# Mother_Board_FPGA.net
KiCad netlist of a schematic drawn in Altium Designer
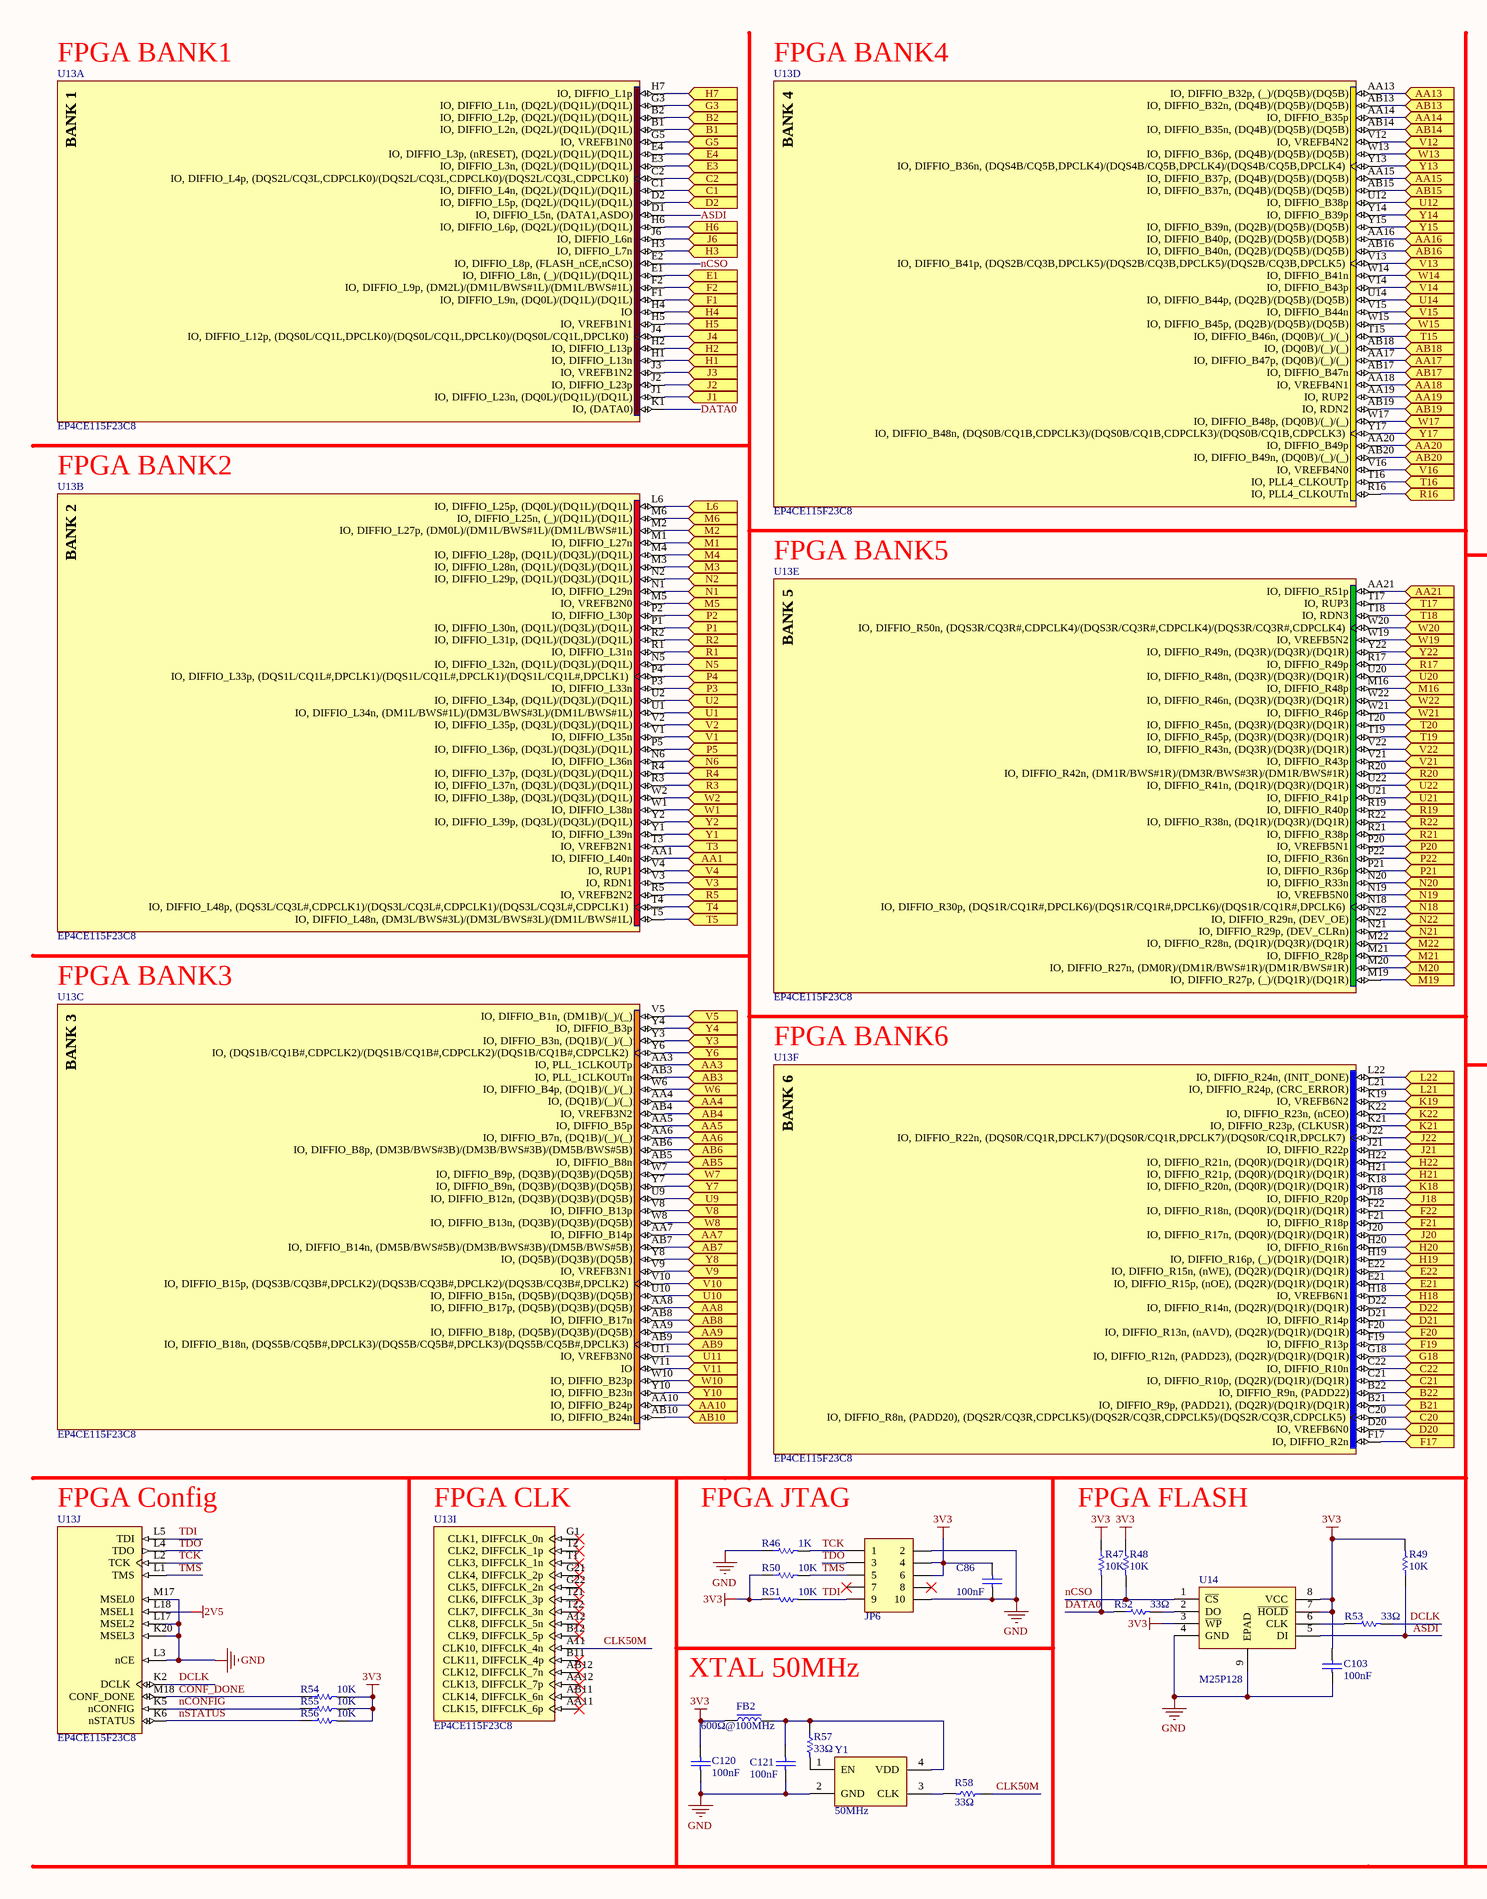
[diagram p0: Mother Board FPGA.SchDoc, left]
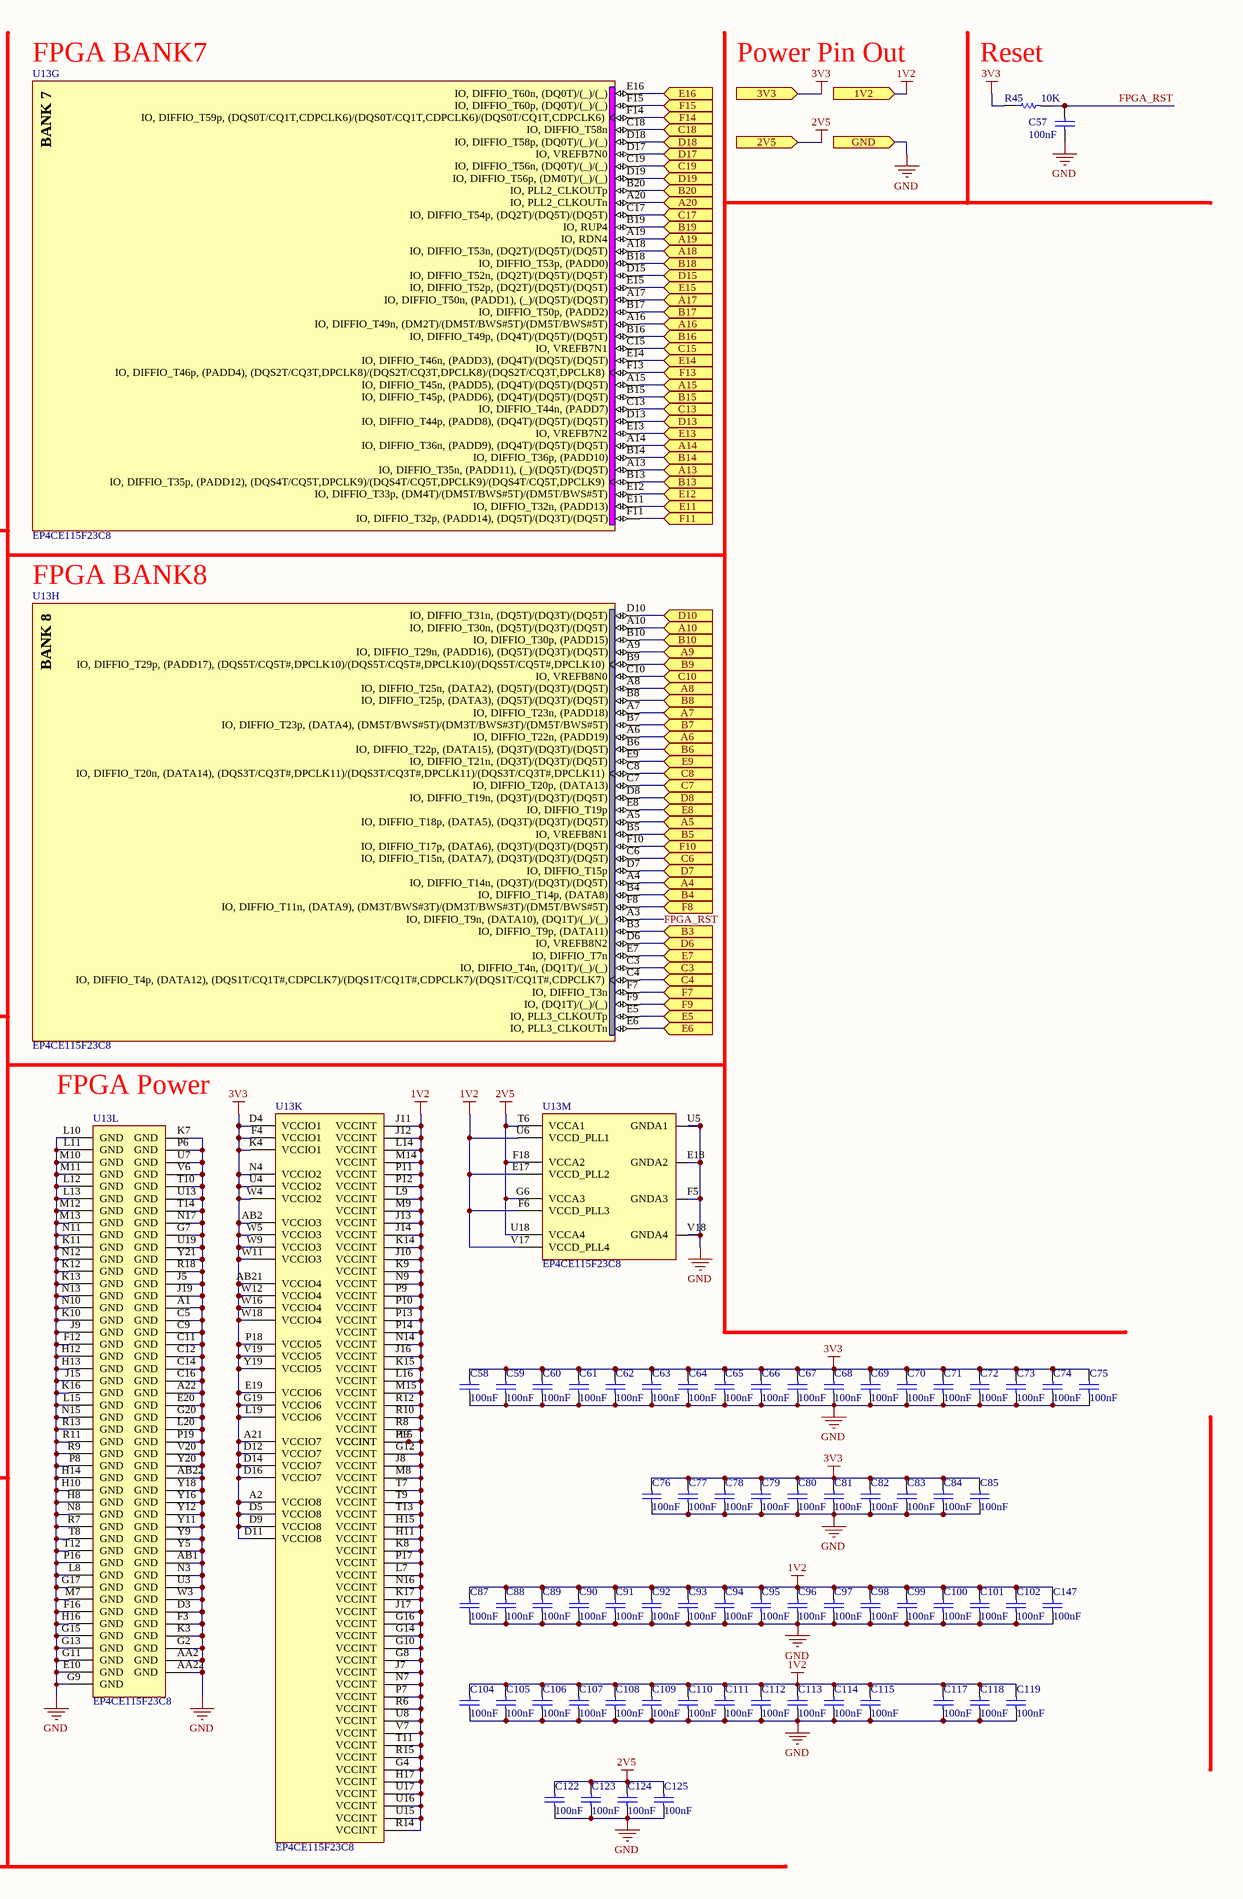
[diagram p1: Mother Board FPGA.SchDoc, right]

(export (version "E")
  (design (tool "Eeschema 10.0.6"))
  (components
    (comp (ref "C57") (value "100nF") (footprint "C0402") (libsource (lib "Cap") (part "Cap")))
    (comp (ref "C58") (value "100nF") (footprint "C0402") (libsource (lib "Cap") (part "Cap")))
    (comp (ref "C59") (value "100nF") (footprint "C0402") (libsource (lib "Cap") (part "Cap")))
    (comp (ref "C60") (value "100nF") (footprint "C0402") (libsource (lib "Cap") (part "Cap")))
    (comp (ref "C61") (value "100nF") (footprint "C0402") (libsource (lib "Cap") (part "Cap")))
    (comp (ref "C62") (value "100nF") (footprint "C0402") (libsource (lib "Cap") (part "Cap")))
    (comp (ref "C63") (value "100nF") (footprint "C0402") (libsource (lib "Cap") (part "Cap")))
    (comp (ref "C64") (value "100nF") (footprint "C0402") (libsource (lib "Cap") (part "Cap")))
    (comp (ref "C65") (value "100nF") (footprint "C0402") (libsource (lib "Cap") (part "Cap")))
    (comp (ref "C66") (value "100nF") (footprint "C0402") (libsource (lib "Cap") (part "Cap")))
    (comp (ref "C67") (value "100nF") (footprint "C0402") (libsource (lib "Cap") (part "Cap")))
    (comp (ref "C68") (value "100nF") (footprint "C0402") (libsource (lib "Cap") (part "Cap")))
    (comp (ref "C69") (value "100nF") (footprint "C0402") (libsource (lib "Cap") (part "Cap")))
    (comp (ref "C70") (value "100nF") (footprint "C0402") (libsource (lib "Cap") (part "Cap")))
    (comp (ref "C71") (value "100nF") (footprint "C0402") (libsource (lib "Cap") (part "Cap")))
    (comp (ref "C72") (value "100nF") (footprint "C0402") (libsource (lib "Cap") (part "Cap")))
    (comp (ref "C73") (value "100nF") (footprint "C0402") (libsource (lib "Cap") (part "Cap")))
    (comp (ref "C74") (value "100nF") (footprint "C0402") (libsource (lib "Cap") (part "Cap")))
    (comp (ref "C75") (value "100nF") (footprint "C0402") (libsource (lib "Cap") (part "Cap")))
    (comp (ref "C76") (value "100nF") (footprint "C0402") (libsource (lib "Cap") (part "Cap")))
    (comp (ref "C77") (value "100nF") (footprint "C0402") (libsource (lib "Cap") (part "Cap")))
    (comp (ref "C78") (value "100nF") (footprint "C0402") (libsource (lib "Cap") (part "Cap")))
    (comp (ref "C79") (value "100nF") (footprint "C0402") (libsource (lib "Cap") (part "Cap")))
    (comp (ref "C80") (value "100nF") (footprint "C0402") (libsource (lib "Cap") (part "Cap")))
    (comp (ref "C81") (value "100nF") (footprint "C0402") (libsource (lib "Cap") (part "Cap")))
    (comp (ref "C82") (value "100nF") (footprint "C0402") (libsource (lib "Cap") (part "Cap")))
    (comp (ref "C83") (value "100nF") (footprint "C0402") (libsource (lib "Cap") (part "Cap")))
    (comp (ref "C84") (value "100nF") (footprint "C0402") (libsource (lib "Cap") (part "Cap")))
    (comp (ref "C85") (value "100nF") (footprint "C0402") (libsource (lib "Cap") (part "Cap")))
    (comp (ref "C86") (value "100nF") (footprint "C0603") (libsource (lib "Cap") (part "Cap")))
    (comp (ref "C87") (value "100nF") (footprint "C0402") (libsource (lib "Cap") (part "Cap")))
    (comp (ref "C88") (value "100nF") (footprint "C0402") (libsource (lib "Cap") (part "Cap")))
    (comp (ref "C89") (value "100nF") (footprint "C0402") (libsource (lib "Cap") (part "Cap")))
    (comp (ref "C90") (value "100nF") (footprint "C0402") (libsource (lib "Cap") (part "Cap")))
    (comp (ref "C91") (value "100nF") (footprint "C0402") (libsource (lib "Cap") (part "Cap")))
    (comp (ref "C92") (value "100nF") (footprint "C0402") (libsource (lib "Cap") (part "Cap")))
    (comp (ref "C93") (value "100nF") (footprint "C0402") (libsource (lib "Cap") (part "Cap")))
    (comp (ref "C94") (value "100nF") (footprint "C0402") (libsource (lib "Cap") (part "Cap")))
    (comp (ref "C95") (value "100nF") (footprint "C0402") (libsource (lib "Cap") (part "Cap")))
    (comp (ref "C96") (value "100nF") (footprint "C0402") (libsource (lib "Cap") (part "Cap")))
    (comp (ref "C97") (value "100nF") (footprint "C0402") (libsource (lib "Cap") (part "Cap")))
    (comp (ref "C98") (value "100nF") (footprint "C0402") (libsource (lib "Cap") (part "Cap")))
    (comp (ref "C99") (value "100nF") (footprint "C0402") (libsource (lib "Cap") (part "Cap")))
    (comp (ref "C100") (value "100nF") (footprint "C0402") (libsource (lib "Cap") (part "Cap")))
    (comp (ref "C101") (value "100nF") (footprint "C0402") (libsource (lib "Cap") (part "Cap")))
    (comp (ref "C102") (value "100nF") (footprint "C0402") (libsource (lib "Cap") (part "Cap")))
    (comp (ref "C103") (value "100nF") (footprint "C0603") (libsource (lib "Cap") (part "Cap")))
    (comp (ref "C104") (value "100nF") (footprint "C0402") (libsource (lib "Cap") (part "Cap")))
    (comp (ref "C105") (value "100nF") (footprint "C0402") (libsource (lib "Cap") (part "Cap")))
    (comp (ref "C106") (value "100nF") (footprint "C0402") (libsource (lib "Cap") (part "Cap")))
    (comp (ref "C107") (value "100nF") (footprint "C0402") (libsource (lib "Cap") (part "Cap")))
    (comp (ref "C108") (value "100nF") (footprint "C0402") (libsource (lib "Cap") (part "Cap")))
    (comp (ref "C109") (value "100nF") (footprint "C0402") (libsource (lib "Cap") (part "Cap")))
    (comp (ref "C110") (value "100nF") (footprint "C0402") (libsource (lib "Cap") (part "Cap")))
    (comp (ref "C111") (value "100nF") (footprint "C0402") (libsource (lib "Cap") (part "Cap")))
    (comp (ref "C112") (value "100nF") (footprint "C0402") (libsource (lib "Cap") (part "Cap")))
    (comp (ref "C113") (value "100nF") (footprint "C0402") (libsource (lib "Cap") (part "Cap")))
    (comp (ref "C114") (value "100nF") (footprint "C0402") (libsource (lib "Cap") (part "Cap")))
    (comp (ref "C115") (value "100nF") (footprint "C0402") (libsource (lib "Cap") (part "Cap")))
    (comp (ref "C117") (value "100nF") (footprint "C0402") (libsource (lib "Cap") (part "Cap")))
    (comp (ref "C118") (value "100nF") (footprint "C0402") (libsource (lib "Cap") (part "Cap")))
    (comp (ref "C119") (value "100nF") (footprint "C0402") (libsource (lib "Cap") (part "Cap")))
    (comp (ref "C120") (value "100nF") (footprint "C0603") (libsource (lib "Cap") (part "Cap")))
    (comp (ref "C121") (value "100nF") (footprint "C0603") (libsource (lib "Cap") (part "Cap")))
    (comp (ref "C122") (value "100nF") (footprint "C0402") (libsource (lib "Cap") (part "Cap")))
    (comp (ref "C123") (value "100nF") (footprint "C0402") (libsource (lib "Cap") (part "Cap")))
    (comp (ref "C124") (value "100nF") (footprint "C0402") (libsource (lib "Cap") (part "Cap")))
    (comp (ref "C125") (value "100nF") (footprint "C0402") (libsource (lib "Cap") (part "Cap")))
    (comp (ref "C147") (value "100nF") (footprint "C0402") (libsource (lib "Cap") (part "Cap")))
    (comp (ref "FB2")
      (value "600Ω@100MHz")
      (footprint "FB 0603")
      (description "磁珠")
      (libsource (lib "All lib") (part "FB"))
    )
    (comp (ref "JP6")
      (value "Header 5X2")
      (footprint "DC2.54-10P - L2")
      (description "5*2P接插件")
      (fields (field (name "版权归属") "源创客"))
      (libsource (lib "All lib") (part "Header 5PX2"))
    )
    (comp (ref "R45") (value "10K") (footprint "R0402") (libsource (lib "Res") (part "RES")))
    (comp (ref "R46") (value "1K") (footprint "R0603") (libsource (lib "Res") (part "RES")))
    (comp (ref "R47") (value "10K") (footprint "R0603") (libsource (lib "Res") (part "RES")))
    (comp (ref "R48") (value "10K") (footprint "R0603") (libsource (lib "Res") (part "RES")))
    (comp (ref "R49") (value "10K") (footprint "R0603") (libsource (lib "Res") (part "RES")))
    (comp (ref "R50") (value "10K") (footprint "R0603") (libsource (lib "Res") (part "RES")))
    (comp (ref "R51") (value "10K") (footprint "R0603") (libsource (lib "Res") (part "RES")))
    (comp (ref "R52") (value "33Ω") (footprint "R0603") (libsource (lib "Res") (part "RES")))
    (comp (ref "R53") (value "33Ω") (footprint "R0603") (libsource (lib "Res") (part "RES")))
    (comp (ref "R54") (value "10K") (footprint "R0402") (libsource (lib "Res") (part "RES")))
    (comp (ref "R55") (value "10K") (footprint "R0402") (libsource (lib "Res") (part "RES")))
    (comp (ref "R56") (value "10K") (footprint "R0402") (libsource (lib "Res") (part "RES")))
    (comp (ref "R57") (value "33Ω") (footprint "R0603") (libsource (lib "Res") (part "RES")))
    (comp (ref "R58") (value "33Ω") (footprint "R0603") (libsource (lib "Res") (part "RES")))
    (comp (ref "U13")
      (value "EP4CE115F23C8")
      (footprint "FBGA484")
      (fields (field (name "PUBLISHER") "Altium Limited"))
      (libsource (lib "All lib") (part "EP4CE115F23C8"))
    )
    (comp (ref "U14")
      (value "M25P128")
      (footprint "WSON8_8X6_MRN")
      (description "外置Flash")
      (fields (field (name "版权归属") "源创客"))
      (libsource (lib "All lib") (part "M25Pxx"))
    )
    (comp (ref "Y1")
      (value "50MHz")
      (footprint "XTAL-3225")
      (description "4脚有源晶振")
      (libsource (lib "All lib") (part "XTAL-4-Power"))
    )
  )
  (nets
    (net (code "1") (name "/A4") (class "Default")
      (node (ref "U13") (pin "A4") (pinfunction "IO,_DIFFIO_T14n,_(DQ3T)/(DQ3T)/(DQ5T)_A4") (pintype "bidirectional"))
    )
    (net (code "2") (name "/A5") (class "Default")
      (node (ref "U13") (pin "A5") (pinfunction "IO,_DIFFIO_T18p,_(DATA5),_(DQ3T)/(DQ3T)/(DQ5T)_A5") (pintype "bidirectional"))
    )
    (net (code "3") (name "/A6") (class "Default")
      (node (ref "U13") (pin "A6") (pinfunction "IO,_DIFFIO_T22n,_(PADD19)_A6") (pintype "bidirectional"))
    )
    (net (code "4") (name "/A7") (class "Default")
      (node (ref "U13") (pin "A7") (pinfunction "IO,_DIFFIO_T23n,_(PADD18)_A7") (pintype "bidirectional"))
    )
    (net (code "5") (name "/A8") (class "Default")
      (node (ref "U13") (pin "A8") (pinfunction "IO,_DIFFIO_T25n,_(DATA2),_(DQ5T)/(DQ3T)/(DQ5T)_A8") (pintype "bidirectional"))
    )
    (net (code "6") (name "/A9") (class "Default")
      (node (ref "U13") (pin "A9") (pinfunction "IO,_DIFFIO_T29n,_(PADD16),_(DQ5T)/(DQ3T)/(DQ5T)_A9") (pintype "bidirectional"))
    )
    (net (code "7") (name "/A10") (class "Default")
      (node (ref "U13") (pin "A10") (pinfunction "IO,_DIFFIO_T30n,_(DQ5T)/(DQ3T)/(DQ5T)_A10") (pintype "bidirectional"))
    )
    (net (code "8") (name "/A13") (class "Default")
      (node (ref "U13") (pin "A13") (pinfunction "IO,_DIFFIO_T35n,_(PADD11),_(_)/(DQ5T)/(DQ5T)_A13") (pintype "bidirectional"))
    )
    (net (code "9") (name "/A14") (class "Default")
      (node (ref "U13") (pin "A14") (pinfunction "IO,_DIFFIO_T36n,_(PADD9),_(DQ4T)/(DQ5T)/(DQ5T)_A14") (pintype "bidirectional"))
    )
    (net (code "10") (name "/A15") (class "Default")
      (node (ref "U13") (pin "A15") (pinfunction "IO,_DIFFIO_T45n,_(PADD5),_(DQ4T)/(DQ5T)/(DQ5T)_A15") (pintype "bidirectional"))
    )
    (net (code "11") (name "/A16") (class "Default")
      (node (ref "U13") (pin "A16") (pinfunction "IO,_DIFFIO_T49n,_(DM2T)/(DM5T/BWS#5T)/(DM5T/BWS#5T)_A16") (pintype "bidirectional"))
    )
    (net (code "12") (name "/A17") (class "Default")
      (node (ref "U13") (pin "A17") (pinfunction "IO,_DIFFIO_T50n,_(PADD1),_(_)/(DQ5T)/(DQ5T)_A17") (pintype "bidirectional"))
    )
    (net (code "13") (name "/A18") (class "Default")
      (node (ref "U13") (pin "A18") (pinfunction "IO,_DIFFIO_T53n,_(DQ2T)/(DQ5T)/(DQ5T)_A18") (pintype "bidirectional"))
    )
    (net (code "14") (name "/A19") (class "Default")
      (node (ref "U13") (pin "A19") (pinfunction "IO,_RDN4_A19") (pintype "bidirectional"))
    )
    (net (code "15") (name "/A20") (class "Default")
      (node (ref "U13") (pin "A20") (pinfunction "IO,_PLL2_CLKOUTn_A20") (pintype "bidirectional"))
    )
    (net (code "16") (name "/AA1") (class "Default")
      (node (ref "U13") (pin "AA1") (pinfunction "IO,_DIFFIO_L40n_AA1") (pintype "bidirectional"))
    )
    (net (code "17") (name "/AA3") (class "Default")
      (node (ref "U13") (pin "AA3") (pinfunction "IO,_PLL_1CLKOUTp_AA3") (pintype "bidirectional"))
    )
    (net (code "18") (name "/AA4") (class "Default")
      (node (ref "U13") (pin "AA4") (pinfunction "IO,_(DQ1B)/(_)/(_)_AA4") (pintype "bidirectional"))
    )
    (net (code "19") (name "/AA5") (class "Default")
      (node (ref "U13") (pin "AA5") (pinfunction "IO,_DIFFIO_B5p_AA5") (pintype "bidirectional"))
    )
    (net (code "20") (name "/AA6") (class "Default")
      (node (ref "U13") (pin "AA6") (pinfunction "IO,_DIFFIO_B7n,_(DQ1B)/(_)/(_)_AA6") (pintype "bidirectional"))
    )
    (net (code "21") (name "/AA7") (class "Default")
      (node (ref "U13") (pin "AA7") (pinfunction "IO,_DIFFIO_B14p_AA7") (pintype "bidirectional"))
    )
    (net (code "22") (name "/AA8") (class "Default")
      (node (ref "U13") (pin "AA8") (pinfunction "IO,_DIFFIO_B17p,_(DQ5B)/(DQ3B)/(DQ5B)_AA8") (pintype "bidirectional"))
    )
    (net (code "23") (name "/AA9") (class "Default")
      (node (ref "U13") (pin "AA9") (pinfunction "IO,_DIFFIO_B18p,_(DQ5B)/(DQ3B)/(DQ5B)_AA9") (pintype "bidirectional"))
    )
    (net (code "24") (name "/AA10") (class "Default")
      (node (ref "U13") (pin "AA10") (pinfunction "IO,_DIFFIO_B24p_AA10") (pintype "bidirectional"))
    )
    (net (code "25") (name "/AA13") (class "Default")
      (node (ref "U13") (pin "AA13") (pinfunction "IO,_DIFFIO_B32p,_(_)/(DQ5B)/(DQ5B)_AA13") (pintype "bidirectional"))
    )
    (net (code "26") (name "/AA14") (class "Default")
      (node (ref "U13") (pin "AA14") (pinfunction "IO,_DIFFIO_B35p_AA14") (pintype "bidirectional"))
    )
    (net (code "27") (name "/AA15") (class "Default")
      (node (ref "U13") (pin "AA15") (pinfunction "IO,_DIFFIO_B37p,_(DQ4B)/(DQ5B)/(DQ5B)_AA15") (pintype "bidirectional"))
    )
    (net (code "28") (name "/AA16") (class "Default")
      (node (ref "U13") (pin "AA16") (pinfunction "IO,_DIFFIO_B40p,_(DQ2B)/(DQ5B)/(DQ5B)_AA16") (pintype "bidirectional"))
    )
    (net (code "29") (name "/AA17") (class "Default")
      (node (ref "U13") (pin "AA17") (pinfunction "IO,_DIFFIO_B47p,_(DQ0B)/(_)/(_)_AA17") (pintype "bidirectional"))
    )
    (net (code "30") (name "/AA18") (class "Default")
      (node (ref "U13") (pin "AA18") (pinfunction "IO,_VREFB4N1_AA18") (pintype "bidirectional"))
    )
    (net (code "31") (name "/AA19") (class "Default")
      (node (ref "U13") (pin "AA19") (pinfunction "IO,_RUP2_AA19") (pintype "bidirectional"))
    )
    (net (code "32") (name "/AA20") (class "Default")
      (node (ref "U13") (pin "AA20") (pinfunction "IO,_DIFFIO_B49p_AA20") (pintype "bidirectional"))
    )
    (net (code "33") (name "/AA21") (class "Default")
      (node (ref "U13") (pin "AA21") (pinfunction "IO,_DIFFIO_R51p_AA21") (pintype "bidirectional"))
    )
    (net (code "34") (name "/AB3") (class "Default")
      (node (ref "U13") (pin "AB3") (pinfunction "IO,_PLL_1CLKOUTn_AB3") (pintype "bidirectional"))
    )
    (net (code "35") (name "/AB4") (class "Default")
      (node (ref "U13") (pin "AB4") (pinfunction "IO,_VREFB3N2_AB4") (pintype "bidirectional"))
    )
    (net (code "36") (name "/AB5") (class "Default")
      (node (ref "U13") (pin "AB5") (pinfunction "IO,_DIFFIO_B8n_AB5") (pintype "bidirectional"))
    )
    (net (code "37") (name "/AB6") (class "Default")
      (node (ref "U13") (pin "AB6") (pinfunction "IO,_DIFFIO_B8p,_(DM3B/BWS#3B)/(DM3B/BWS#3B)/(DM5B/BWS#5B)_AB6") (pintype "bidirectional"))
    )
    (net (code "38") (name "/AB7") (class "Default")
      (node (ref "U13") (pin "AB7") (pinfunction "IO,_DIFFIO_B14n,_(DM5B/BWS#5B)/(DM3B/BWS#3B)/(DM5B/BWS#5B)_AB7") (pintype "bidirectional"))
    )
    (net (code "39") (name "/AB8") (class "Default")
      (node (ref "U13") (pin "AB8") (pinfunction "IO,_DIFFIO_B17n_AB8") (pintype "bidirectional"))
    )
    (net (code "40") (name "/AB9") (class "Default")
      (node (ref "U13") (pin "AB9") (pinfunction "IO,_DIFFIO_B18n,_(DQS5B/CQ5B#,DPCLK3)/(DQS5B/CQ5B#,DPCLK3)/(DQS5B/CQ5B#,DPCLK3)_AB9") (pintype "bidirectional"))
    )
    (net (code "41") (name "/AB10") (class "Default")
      (node (ref "U13") (pin "AB10") (pinfunction "IO,_DIFFIO_B24n_AB10") (pintype "bidirectional"))
    )
    (net (code "42") (name "/AB13") (class "Default")
      (node (ref "U13") (pin "AB13") (pinfunction "IO,_DIFFIO_B32n,_(DQ4B)/(DQ5B)/(DQ5B)_AB13") (pintype "bidirectional"))
    )
    (net (code "43") (name "/AB14") (class "Default")
      (node (ref "U13") (pin "AB14") (pinfunction "IO,_DIFFIO_B35n,_(DQ4B)/(DQ5B)/(DQ5B)_AB14") (pintype "bidirectional"))
    )
    (net (code "44") (name "/AB15") (class "Default")
      (node (ref "U13") (pin "AB15") (pinfunction "IO,_DIFFIO_B37n,_(DQ4B)/(DQ5B)/(DQ5B)_AB15") (pintype "bidirectional"))
    )
    (net (code "45") (name "/AB16") (class "Default")
      (node (ref "U13") (pin "AB16") (pinfunction "IO,_DIFFIO_B40n,_(DQ2B)/(DQ5B)/(DQ5B)_AB16") (pintype "bidirectional"))
    )
    (net (code "46") (name "/AB17") (class "Default")
      (node (ref "U13") (pin "AB17") (pinfunction "IO,_DIFFIO_B47n_AB17") (pintype "bidirectional"))
    )
    (net (code "47") (name "/AB18") (class "Default")
      (node (ref "U13") (pin "AB18") (pinfunction "IO,_(DQ0B)/(_)/(_)_AB18") (pintype "bidirectional"))
    )
    (net (code "48") (name "/AB19") (class "Default")
      (node (ref "U13") (pin "AB19") (pinfunction "IO,_RDN2_AB19") (pintype "bidirectional"))
    )
    (net (code "49") (name "/AB20") (class "Default")
      (node (ref "U13") (pin "AB20") (pinfunction "IO,_DIFFIO_B49n,_(DQ0B)/(_)/(_)_AB20") (pintype "bidirectional"))
    )
    (net (code "50") (name "/ASDI") (class "Default")
      (node (ref "R49") (pin "1") (pinfunction "1_1") (pintype "passive"))
      (node (ref "U13") (pin "D1") (pinfunction "IO,_DIFFIO_L5n,_(DATA1,ASDO)_D1") (pintype "bidirectional"))
      (node (ref "U14") (pin "5") (pinfunction "DI_5") (pintype "passive"))
    )
    (net (code "51") (name "/B1") (class "Default")
      (node (ref "U13") (pin "B1") (pinfunction "IO,_DIFFIO_L2n,_(DQ2L)/(DQ1L)/(DQ1L)_B1") (pintype "bidirectional"))
    )
    (net (code "52") (name "/B2") (class "Default")
      (node (ref "U13") (pin "B2") (pinfunction "IO,_DIFFIO_L2p,_(DQ2L)/(DQ1L)/(DQ1L)_B2") (pintype "bidirectional"))
    )
    (net (code "53") (name "/B3") (class "Default")
      (node (ref "U13") (pin "B3") (pinfunction "IO,_DIFFIO_T9p,_(DATA11)_B3") (pintype "bidirectional"))
    )
    (net (code "54") (name "/B4") (class "Default")
      (node (ref "U13") (pin "B4") (pinfunction "IO,_DIFFIO_T14p,_(DATA8)_B4") (pintype "bidirectional"))
    )
    (net (code "55") (name "/B5") (class "Default")
      (node (ref "U13") (pin "B5") (pinfunction "IO,_VREFB8N1_B5") (pintype "bidirectional"))
    )
    (net (code "56") (name "/B6") (class "Default")
      (node (ref "U13") (pin "B6") (pinfunction "IO,_DIFFIO_T22p,_(DATA15),_(DQ3T)/(DQ3T)/(DQ5T)_B6") (pintype "bidirectional"))
    )
    (net (code "57") (name "/B7") (class "Default")
      (node (ref "U13") (pin "B7") (pinfunction "IO,_DIFFIO_T23p,_(DATA4),_(DM5T/BWS#5T)/(DM3T/BWS#3T)/(DM5T/BWS#5T)_B7") (pintype "bidirectional"))
    )
    (net (code "58") (name "/B8") (class "Default")
      (node (ref "U13") (pin "B8") (pinfunction "IO,_DIFFIO_T25p,_(DATA3),_(DQ5T)/(DQ3T)/(DQ5T)_B8") (pintype "bidirectional"))
    )
    (net (code "59") (name "/B9") (class "Default")
      (node (ref "U13") (pin "B9") (pinfunction "IO,_DIFFIO_T29p,_(PADD17),_(DQS5T/CQ5T#,DPCLK10)/(DQS5T/CQ5T#,DPCLK10)/(DQS5T/CQ5T#,DPCLK10)_B9") (pintype "bidirectional"))
    )
    (net (code "60") (name "/B10") (class "Default")
      (node (ref "U13") (pin "B10") (pinfunction "IO,_DIFFIO_T30p,_(PADD15)_B10") (pintype "bidirectional"))
    )
    (net (code "61") (name "/B13") (class "Default")
      (node (ref "U13") (pin "B13") (pinfunction "IO,_DIFFIO_T35p,_(PADD12),_(DQS4T/CQ5T,DPCLK9)/(DQS4T/CQ5T,DPCLK9)/(DQS4T/CQ5T,DPCLK9)_B13") (pintype "bidirectional"))
    )
    (net (code "62") (name "/B14") (class "Default")
      (node (ref "U13") (pin "B14") (pinfunction "IO,_DIFFIO_T36p,_(PADD10)_B14") (pintype "bidirectional"))
    )
    (net (code "63") (name "/B15") (class "Default")
      (node (ref "U13") (pin "B15") (pinfunction "IO,_DIFFIO_T45p,_(PADD6),_(DQ4T)/(DQ5T)/(DQ5T)_B15") (pintype "bidirectional"))
    )
    (net (code "64") (name "/B16") (class "Default")
      (node (ref "U13") (pin "B16") (pinfunction "IO,_DIFFIO_T49p,_(DQ4T)/(DQ5T)/(DQ5T)_B16") (pintype "bidirectional"))
    )
    (net (code "65") (name "/B17") (class "Default")
      (node (ref "U13") (pin "B17") (pinfunction "IO,_DIFFIO_T50p,_(PADD2)_B17") (pintype "bidirectional"))
    )
    (net (code "66") (name "/B18") (class "Default")
      (node (ref "U13") (pin "B18") (pinfunction "IO,_DIFFIO_T53p,_(PADD0)_B18") (pintype "bidirectional"))
    )
    (net (code "67") (name "/B19") (class "Default")
      (node (ref "U13") (pin "B19") (pinfunction "IO,_RUP4_B19") (pintype "bidirectional"))
    )
    (net (code "68") (name "/B20") (class "Default")
      (node (ref "U13") (pin "B20") (pinfunction "IO,_PLL2_CLKOUTp_B20") (pintype "bidirectional"))
    )
    (net (code "69") (name "/B21") (class "Default")
      (node (ref "U13") (pin "B21") (pinfunction "IO,_DIFFIO_R9p,_(PADD21),_(DQ2R)/(DQ1R)/(DQ1R)_B21") (pintype "bidirectional"))
    )
    (net (code "70") (name "/B22") (class "Default")
      (node (ref "U13") (pin "B22") (pinfunction "IO,_DIFFIO_R9n,_(PADD22)_B22") (pintype "bidirectional"))
    )
    (net (code "71") (name "/C1") (class "Default")
      (node (ref "U13") (pin "C1") (pinfunction "IO,_DIFFIO_L4n,_(DQ2L)/(DQ1L)/(DQ1L)_C1") (pintype "bidirectional"))
    )
    (net (code "72") (name "/C2") (class "Default")
      (node (ref "U13") (pin "C2") (pinfunction "IO,_DIFFIO_L4p,_(DQS2L/CQ3L,CDPCLK0)/(DQS2L/CQ3L,CDPCLK0)/(DQS2L/CQ3L,CDPCLK0)_C2") (pintype "bidirectional"))
    )
    (net (code "73") (name "/C3") (class "Default")
      (node (ref "U13") (pin "C3") (pinfunction "IO,_DIFFIO_T4n,_(DQ1T)/(_)/(_)_C3") (pintype "bidirectional"))
    )
    (net (code "74") (name "/C4") (class "Default")
      (node (ref "U13") (pin "C4") (pinfunction "IO,_DIFFIO_T4p,_(DATA12),_(DQS1T/CQ1T#,CDPCLK7)/(DQS1T/CQ1T#,CDPCLK7)/(DQS1T/CQ1T#,CDPCLK7)_C4") (pintype "bidirectional"))
    )
    (net (code "75") (name "/C6") (class "Default")
      (node (ref "U13") (pin "C6") (pinfunction "IO,_DIFFIO_T15n,_(DATA7),_(DQ3T)/(DQ3T)/(DQ5T)_C6") (pintype "bidirectional"))
    )
    (net (code "76") (name "/C7") (class "Default")
      (node (ref "U13") (pin "C7") (pinfunction "IO,_DIFFIO_T20p,_(DATA13)_C7") (pintype "bidirectional"))
    )
    (net (code "77") (name "/C8") (class "Default")
      (node (ref "U13") (pin "C8") (pinfunction "IO,_DIFFIO_T20n,_(DATA14),_(DQS3T/CQ3T#,DPCLK11)/(DQS3T/CQ3T#,DPCLK11)/(DQS3T/CQ3T#,DPCLK11)_C8") (pintype "bidirectional"))
    )
    (net (code "78") (name "/C10") (class "Default")
      (node (ref "U13") (pin "C10") (pinfunction "IO,_VREFB8N0_C10") (pintype "bidirectional"))
    )
    (net (code "79") (name "/C13") (class "Default")
      (node (ref "U13") (pin "C13") (pinfunction "IO,_DIFFIO_T44n,_(PADD7)_C13") (pintype "bidirectional"))
    )
    (net (code "80") (name "/C15") (class "Default")
      (node (ref "U13") (pin "C15") (pinfunction "IO,_VREFB7N1_C15") (pintype "bidirectional"))
    )
    (net (code "81") (name "/C17") (class "Default")
      (node (ref "U13") (pin "C17") (pinfunction "IO,_DIFFIO_T54p,_(DQ2T)/(DQ5T)/(DQ5T)_C17") (pintype "bidirectional"))
    )
    (net (code "82") (name "/C18") (class "Default")
      (node (ref "U13") (pin "C18") (pinfunction "IO,_DIFFIO_T58n_C18") (pintype "bidirectional"))
    )
    (net (code "83") (name "/C19") (class "Default")
      (node (ref "U13") (pin "C19") (pinfunction "IO,_DIFFIO_T56n,_(DQ0T)/(_)/(_)_C19") (pintype "bidirectional"))
    )
    (net (code "84") (name "/C20") (class "Default")
      (node (ref "U13") (pin "C20") (pinfunction "IO,_DIFFIO_R8n,_(PADD20),_(DQS2R/CQ3R,CDPCLK5)/(DQS2R/CQ3R,CDPCLK5)/(DQS2R/CQ3R,CDPCLK5)_C20") (pintype "bidirectional"))
    )
    (net (code "85") (name "/C21") (class "Default")
      (node (ref "U13") (pin "C21") (pinfunction "IO,_DIFFIO_R10p,_(DQ2R)/(DQ1R)/(DQ1R)_C21") (pintype "bidirectional"))
    )
    (net (code "86") (name "/C22") (class "Default")
      (node (ref "U13") (pin "C22") (pinfunction "IO,_DIFFIO_R10n_C22") (pintype "bidirectional"))
    )
    (net (code "87") (name "/CLK50M") (class "Default")
      (node (ref "R58") (pin "1") (pinfunction "1_1") (pintype "passive"))
      (node (ref "U13") (pin "A11") (pinfunction "CLK10,_DIFFCLK_4n_A11") (pintype "input"))
    )
    (net (code "88") (name "/CONF_DONE") (class "Default")
      (node (ref "R54") (pin "1") (pinfunction "1_1") (pintype "passive"))
      (node (ref "U13") (pin "M18") (pinfunction "CONF_DONE_M18") (pintype "bidirectional"))
    )
    (net (code "89") (name "/D2") (class "Default")
      (node (ref "U13") (pin "D2") (pinfunction "IO,_DIFFIO_L5p,_(DQ2L)/(DQ1L)/(DQ1L)_D2") (pintype "bidirectional"))
    )
    (net (code "90") (name "/D6") (class "Default")
      (node (ref "U13") (pin "D6") (pinfunction "IO,_VREFB8N2_D6") (pintype "bidirectional"))
    )
    (net (code "91") (name "/D7") (class "Default")
      (node (ref "U13") (pin "D7") (pinfunction "IO,_DIFFIO_T15p_D7") (pintype "bidirectional"))
    )
    (net (code "92") (name "/D8") (class "Default")
      (node (ref "U13") (pin "D8") (pinfunction "IO,_DIFFIO_T19n,_(DQ3T)/(DQ3T)/(DQ5T)_D8") (pintype "bidirectional"))
    )
    (net (code "93") (name "/D10") (class "Default")
      (node (ref "U13") (pin "D10") (pinfunction "IO,_DIFFIO_T31n,_(DQ5T)/(DQ3T)/(DQ5T)_D10") (pintype "bidirectional"))
    )
    (net (code "94") (name "/D13") (class "Default")
      (node (ref "U13") (pin "D13") (pinfunction "IO,_DIFFIO_T44p,_(PADD8),_(DQ4T)/(DQ5T)/(DQ5T)_D13") (pintype "bidirectional"))
    )
    (net (code "95") (name "/D15") (class "Default")
      (node (ref "U13") (pin "D15") (pinfunction "IO,_DIFFIO_T52n,_(DQ2T)/(DQ5T)/(DQ5T)_D15") (pintype "bidirectional"))
    )
    (net (code "96") (name "/D17") (class "Default")
      (node (ref "U13") (pin "D17") (pinfunction "IO,_VREFB7N0_D17") (pintype "bidirectional"))
    )
    (net (code "97") (name "/D18") (class "Default")
      (node (ref "U13") (pin "D18") (pinfunction "IO,_DIFFIO_T58p,_(DQ0T)/(_)/(_)_D18") (pintype "bidirectional"))
    )
    (net (code "98") (name "/D19") (class "Default")
      (node (ref "U13") (pin "D19") (pinfunction "IO,_DIFFIO_T56p,_(DM0T)/(_)/(_)_D19") (pintype "bidirectional"))
    )
    (net (code "99") (name "/D20") (class "Default")
      (node (ref "U13") (pin "D20") (pinfunction "IO,_VREFB6N0_D20") (pintype "bidirectional"))
    )
    (net (code "100") (name "/D21") (class "Default")
      (node (ref "U13") (pin "D21") (pinfunction "IO,_DIFFIO_R14p_D21") (pintype "bidirectional"))
    )
    (net (code "101") (name "/D22") (class "Default")
      (node (ref "U13") (pin "D22") (pinfunction "IO,_DIFFIO_R14n,_(DQ2R)/(DQ1R)/(DQ1R)_D22") (pintype "bidirectional"))
    )
    (net (code "102") (name "/DATA0") (class "Default")
      (node (ref "R47") (pin "2") (pinfunction "2_2") (pintype "passive"))
      (node (ref "R52") (pin "1") (pinfunction "1_1") (pintype "passive"))
      (node (ref "U13") (pin "K1") (pinfunction "IO,_(DATA0)_K1") (pintype "bidirectional"))
    )
    (net (code "103") (name "/DCLK") (class "Default")
      (node (ref "R53") (pin "2") (pinfunction "2_2") (pintype "passive"))
      (node (ref "U13") (pin "K2") (pinfunction "DCLK_K2") (pintype "bidirectional"))
    )
    (net (code "104") (name "/E1") (class "Default")
      (node (ref "U13") (pin "E1") (pinfunction "IO,_DIFFIO_L8n,_(_)/(DQ1L)/(DQ1L)_E1") (pintype "bidirectional"))
    )
    (net (code "105") (name "/E3") (class "Default")
      (node (ref "U13") (pin "E3") (pinfunction "IO,_DIFFIO_L3n,_(DQ2L)/(DQ1L)/(DQ1L)_E3") (pintype "bidirectional"))
    )
    (net (code "106") (name "/E4") (class "Default")
      (node (ref "U13") (pin "E4") (pinfunction "IO,_DIFFIO_L3p,_(nRESET),_(DQ2L)/(DQ1L)/(DQ1L)_E4") (pintype "bidirectional"))
    )
    (net (code "107") (name "/E5") (class "Default")
      (node (ref "U13") (pin "E5") (pinfunction "IO,_PLL3_CLKOUTp_E5") (pintype "bidirectional"))
    )
    (net (code "108") (name "/E6") (class "Default")
      (node (ref "U13") (pin "E6") (pinfunction "IO,_PLL3_CLKOUTn_E6") (pintype "bidirectional"))
    )
    (net (code "109") (name "/E7") (class "Default")
      (node (ref "U13") (pin "E7") (pinfunction "IO,_DIFFIO_T7n_E7") (pintype "bidirectional"))
    )
    (net (code "110") (name "/E8") (class "Default")
      (node (ref "U13") (pin "E8") (pinfunction "IO,_DIFFIO_T19p_E8") (pintype "bidirectional"))
    )
    (net (code "111") (name "/E9") (class "Default")
      (node (ref "U13") (pin "E9") (pinfunction "IO,_DIFFIO_T21n,_(DQ3T)/(DQ3T)/(DQ5T)_E9") (pintype "bidirectional"))
    )
    (net (code "112") (name "/E11") (class "Default")
      (node (ref "U13") (pin "E11") (pinfunction "IO,_DIFFIO_T32n,_(PADD13)_E11") (pintype "bidirectional"))
    )
    (net (code "113") (name "/E12") (class "Default")
      (node (ref "U13") (pin "E12") (pinfunction "IO,_DIFFIO_T33p,_(DM4T)/(DM5T/BWS#5T)/(DM5T/BWS#5T)_E12") (pintype "bidirectional"))
    )
    (net (code "114") (name "/E13") (class "Default")
      (node (ref "U13") (pin "E13") (pinfunction "IO,_VREFB7N2_E13") (pintype "bidirectional"))
    )
    (net (code "115") (name "/E14") (class "Default")
      (node (ref "U13") (pin "E14") (pinfunction "IO,_DIFFIO_T46n,_(PADD3),_(DQ4T)/(DQ5T)/(DQ5T)_E14") (pintype "bidirectional"))
    )
    (net (code "116") (name "/E15") (class "Default")
      (node (ref "U13") (pin "E15") (pinfunction "IO,_DIFFIO_T52p,_(DQ2T)/(DQ5T)/(DQ5T)_E15") (pintype "bidirectional"))
    )
    (net (code "117") (name "/E16") (class "Default")
      (node (ref "U13") (pin "E16") (pinfunction "IO,_DIFFIO_T60n,_(DQ0T)/(_)/(_)_E16") (pintype "bidirectional"))
    )
    (net (code "118") (name "/E21") (class "Default")
      (node (ref "U13") (pin "E21") (pinfunction "IO,_DIFFIO_R15p,_(nOE),_(DQ2R)/(DQ1R)/(DQ1R)_E21") (pintype "bidirectional"))
    )
    (net (code "119") (name "/E22") (class "Default")
      (node (ref "U13") (pin "E22") (pinfunction "IO,_DIFFIO_R15n,_(nWE),_(DQ2R)/(DQ1R)/(DQ1R)_E22") (pintype "bidirectional"))
    )
    (net (code "120") (name "/F1") (class "Default")
      (node (ref "U13") (pin "F1") (pinfunction "IO,_DIFFIO_L9n,_(DQ0L)/(DQ1L)/(DQ1L)_F1") (pintype "bidirectional"))
    )
    (net (code "121") (name "/F2") (class "Default")
      (node (ref "U13") (pin "F2") (pinfunction "IO,_DIFFIO_L9p,_(DM2L)/(DM1L/BWS#1L)/(DM1L/BWS#1L)_F2") (pintype "bidirectional"))
    )
    (net (code "122") (name "/F7") (class "Default")
      (node (ref "U13") (pin "F7") (pinfunction "IO,_DIFFIO_T3n_F7") (pintype "bidirectional"))
    )
    (net (code "123") (name "/F8") (class "Default")
      (node (ref "U13") (pin "F8") (pinfunction "IO,_DIFFIO_T11n,_(DATA9),_(DM3T/BWS#3T)/(DM3T/BWS#3T)/(DM5T/BWS#5T)_F8") (pintype "bidirectional"))
    )
    (net (code "124") (name "/F9") (class "Default")
      (node (ref "U13") (pin "F9") (pinfunction "IO,_(DQ1T)/(_)/(_)_F9") (pintype "bidirectional"))
    )
    (net (code "125") (name "/F10") (class "Default")
      (node (ref "U13") (pin "F10") (pinfunction "IO,_DIFFIO_T17p,_(DATA6),_(DQ3T)/(DQ3T)/(DQ5T)_F10") (pintype "bidirectional"))
    )
    (net (code "126") (name "/F11") (class "Default")
      (node (ref "U13") (pin "F11") (pinfunction "IO,_DIFFIO_T32p,_(PADD14),_(DQ5T)/(DQ3T)/(DQ5T)_F11") (pintype "bidirectional"))
    )
    (net (code "127") (name "/F13") (class "Default")
      (node (ref "U13") (pin "F13") (pinfunction "IO,_DIFFIO_T46p,_(PADD4),_(DQS2T/CQ3T,DPCLK8)/(DQS2T/CQ3T,DPCLK8)/(DQS2T/CQ3T,DPCLK8)_F13") (pintype "bidirectional"))
    )
    (net (code "128") (name "/F14") (class "Default")
      (node (ref "U13") (pin "F14") (pinfunction "IO,_DIFFIO_T59p,_(DQS0T/CQ1T,CDPCLK6)/(DQS0T/CQ1T,CDPCLK6)/(DQS0T/CQ1T,CDPCLK6)_F14") (pintype "bidirectional"))
    )
    (net (code "129") (name "/F15") (class "Default")
      (node (ref "U13") (pin "F15") (pinfunction "IO,_DIFFIO_T60p,_(DQ0T)/(_)/(_)_F15") (pintype "bidirectional"))
    )
    (net (code "130") (name "/F17") (class "Default")
      (node (ref "U13") (pin "F17") (pinfunction "IO,_DIFFIO_R2n_F17") (pintype "bidirectional"))
    )
    (net (code "131") (name "/F19") (class "Default")
      (node (ref "U13") (pin "F19") (pinfunction "IO,_DIFFIO_R13p_F19") (pintype "bidirectional"))
    )
    (net (code "132") (name "/F20") (class "Default")
      (node (ref "U13") (pin "F20") (pinfunction "IO,_DIFFIO_R13n,_(nAVD),_(DQ2R)/(DQ1R)/(DQ1R)_F20") (pintype "bidirectional"))
    )
    (net (code "133") (name "/F21") (class "Default")
      (node (ref "U13") (pin "F21") (pinfunction "IO,_DIFFIO_R18p_F21") (pintype "bidirectional"))
    )
    (net (code "134") (name "/F22") (class "Default")
      (node (ref "U13") (pin "F22") (pinfunction "IO,_DIFFIO_R18n,_(DQ0R)/(DQ1R)/(DQ1R)_F22") (pintype "bidirectional"))
    )
    (net (code "135") (name "/FPGA_RST") (class "Default")
      (node (ref "C57") (pin "2") (pinfunction "2_2") (pintype "passive"))
      (node (ref "R45") (pin "2") (pinfunction "2_2") (pintype "passive"))
      (node (ref "U13") (pin "A3") (pinfunction "IO,_DIFFIO_T9n,_(DATA10),_(DQ1T)/(_)/(_)_A3") (pintype "bidirectional"))
    )
    (net (code "136") (name "/G3") (class "Default")
      (node (ref "U13") (pin "G3") (pinfunction "IO,_DIFFIO_L1n,_(DQ2L)/(DQ1L)/(DQ1L)_G3") (pintype "bidirectional"))
    )
    (net (code "137") (name "/G5") (class "Default")
      (node (ref "U13") (pin "G5") (pinfunction "IO,_VREFB1N0_G5") (pintype "bidirectional"))
    )
    (net (code "138") (name "/G18") (class "Default")
      (node (ref "U13") (pin "G18") (pinfunction "IO,_DIFFIO_R12n,_(PADD23),_(DQ2R)/(DQ1R)/(DQ1R)_G18") (pintype "bidirectional"))
    )
    (net (code "139") (name "/H1") (class "Default")
      (node (ref "U13") (pin "H1") (pinfunction "IO,_DIFFIO_L13n_H1") (pintype "bidirectional"))
    )
    (net (code "140") (name "/H2") (class "Default")
      (node (ref "U13") (pin "H2") (pinfunction "IO,_DIFFIO_L13p_H2") (pintype "bidirectional"))
    )
    (net (code "141") (name "/H3") (class "Default")
      (node (ref "U13") (pin "H3") (pinfunction "IO,_DIFFIO_L7n_H3") (pintype "bidirectional"))
    )
    (net (code "142") (name "/H4") (class "Default")
      (node (ref "U13") (pin "H4") (pinfunction "IO_H4") (pintype "bidirectional"))
    )
    (net (code "143") (name "/H5") (class "Default")
      (node (ref "U13") (pin "H5") (pinfunction "IO,_VREFB1N1_H5") (pintype "bidirectional"))
    )
    (net (code "144") (name "/H6") (class "Default")
      (node (ref "U13") (pin "H6") (pinfunction "IO,_DIFFIO_L6p,_(DQ2L)/(DQ1L)/(DQ1L)_H6") (pintype "bidirectional"))
    )
    (net (code "145") (name "/H7") (class "Default")
      (node (ref "U13") (pin "H7") (pinfunction "IO,_DIFFIO_L1p_H7") (pintype "bidirectional"))
    )
    (net (code "146") (name "/H18") (class "Default")
      (node (ref "U13") (pin "H18") (pinfunction "IO,_VREFB6N1_H18") (pintype "bidirectional"))
    )
    (net (code "147") (name "/H19") (class "Default")
      (node (ref "U13") (pin "H19") (pinfunction "IO,_DIFFIO_R16p,_(_)/(DQ1R)/(DQ1R)_H19") (pintype "bidirectional"))
    )
    (net (code "148") (name "/H20") (class "Default")
      (node (ref "U13") (pin "H20") (pinfunction "IO,_DIFFIO_R16n_H20") (pintype "bidirectional"))
    )
    (net (code "149") (name "/H21") (class "Default")
      (node (ref "U13") (pin "H21") (pinfunction "IO,_DIFFIO_R21p,_(DQ0R)/(DQ1R)/(DQ1R)_H21") (pintype "bidirectional"))
    )
    (net (code "150") (name "/H22") (class "Default")
      (node (ref "U13") (pin "H22") (pinfunction "IO,_DIFFIO_R21n,_(DQ0R)/(DQ1R)/(DQ1R)_H22") (pintype "bidirectional"))
    )
    (net (code "151") (name "/J1") (class "Default")
      (node (ref "U13") (pin "J1") (pinfunction "IO,_DIFFIO_L23n,_(DQ0L)/(DQ1L)/(DQ1L)_J1") (pintype "bidirectional"))
    )
    (net (code "152") (name "/J2") (class "Default")
      (node (ref "U13") (pin "J2") (pinfunction "IO,_DIFFIO_L23p_J2") (pintype "bidirectional"))
    )
    (net (code "153") (name "/J3") (class "Default")
      (node (ref "U13") (pin "J3") (pinfunction "IO,_VREFB1N2_J3") (pintype "bidirectional"))
    )
    (net (code "154") (name "/J4") (class "Default")
      (node (ref "U13") (pin "J4") (pinfunction "IO,_DIFFIO_L12p,_(DQS0L/CQ1L,DPCLK0)/(DQS0L/CQ1L,DPCLK0)/(DQS0L/CQ1L,DPCLK0)_J4") (pintype "bidirectional"))
    )
    (net (code "155") (name "/J6") (class "Default")
      (node (ref "U13") (pin "J6") (pinfunction "IO,_DIFFIO_L6n_J6") (pintype "bidirectional"))
    )
    (net (code "156") (name "/J18") (class "Default")
      (node (ref "U13") (pin "J18") (pinfunction "IO,_DIFFIO_R20p_J18") (pintype "bidirectional"))
    )
    (net (code "157") (name "/J20") (class "Default")
      (node (ref "U13") (pin "J20") (pinfunction "IO,_DIFFIO_R17n,_(DQ0R)/(DQ1R)/(DQ1R)_J20") (pintype "bidirectional"))
    )
    (net (code "158") (name "/J21") (class "Default")
      (node (ref "U13") (pin "J21") (pinfunction "IO,_DIFFIO_R22p_J21") (pintype "bidirectional"))
    )
    (net (code "159") (name "/J22") (class "Default")
      (node (ref "U13") (pin "J22") (pinfunction "IO,_DIFFIO_R22n,_(DQS0R/CQ1R,DPCLK7)/(DQS0R/CQ1R,DPCLK7)/(DQS0R/CQ1R,DPCLK7)_J22") (pintype "bidirectional"))
    )
    (net (code "160") (name "/K18") (class "Default")
      (node (ref "U13") (pin "K18") (pinfunction "IO,_DIFFIO_R20n,_(DQ0R)/(DQ1R)/(DQ1R)_K18") (pintype "bidirectional"))
    )
    (net (code "161") (name "/K19") (class "Default")
      (node (ref "U13") (pin "K19") (pinfunction "IO,_VREFB6N2_K19") (pintype "bidirectional"))
    )
    (net (code "162") (name "/K21") (class "Default")
      (node (ref "U13") (pin "K21") (pinfunction "IO,_DIFFIO_R23p,_(CLKUSR)_K21") (pintype "bidirectional"))
    )
    (net (code "163") (name "/K22") (class "Default")
      (node (ref "U13") (pin "K22") (pinfunction "IO,_DIFFIO_R23n,_(nCEO)_K22") (pintype "bidirectional"))
    )
    (net (code "164") (name "/L6") (class "Default")
      (node (ref "U13") (pin "L6") (pinfunction "IO,_DIFFIO_L25p,_(DQ0L)/(DQ1L)/(DQ1L)_L6") (pintype "bidirectional"))
    )
    (net (code "165") (name "/L21") (class "Default")
      (node (ref "U13") (pin "L21") (pinfunction "IO,_DIFFIO_R24p,_(CRC_ERROR)_L21") (pintype "bidirectional"))
    )
    (net (code "166") (name "/L22") (class "Default")
      (node (ref "U13") (pin "L22") (pinfunction "IO,_DIFFIO_R24n,_(INIT_DONE)_L22") (pintype "bidirectional"))
    )
    (net (code "167") (name "/M1") (class "Default")
      (node (ref "U13") (pin "M1") (pinfunction "IO,_DIFFIO_L27n_M1") (pintype "bidirectional"))
    )
    (net (code "168") (name "/M2") (class "Default")
      (node (ref "U13") (pin "M2") (pinfunction "IO,_DIFFIO_L27p,_(DM0L)/(DM1L/BWS#1L)/(DM1L/BWS#1L)_M2") (pintype "bidirectional"))
    )
    (net (code "169") (name "/M3") (class "Default")
      (node (ref "U13") (pin "M3") (pinfunction "IO,_DIFFIO_L28n,_(DQ1L)/(DQ3L)/(DQ1L)_M3") (pintype "bidirectional"))
    )
    (net (code "170") (name "/M4") (class "Default")
      (node (ref "U13") (pin "M4") (pinfunction "IO,_DIFFIO_L28p,_(DQ1L)/(DQ3L)/(DQ1L)_M4") (pintype "bidirectional"))
    )
    (net (code "171") (name "/M5") (class "Default")
      (node (ref "U13") (pin "M5") (pinfunction "IO,_VREFB2N0_M5") (pintype "bidirectional"))
    )
    (net (code "172") (name "/M6") (class "Default")
      (node (ref "U13") (pin "M6") (pinfunction "IO,_DIFFIO_L25n,_(_)/(DQ1L)/(DQ1L)_M6") (pintype "bidirectional"))
    )
    (net (code "173") (name "/M16") (class "Default")
      (node (ref "U13") (pin "M16") (pinfunction "IO,_DIFFIO_R48p_M16") (pintype "bidirectional"))
    )
    (net (code "174") (name "/M19") (class "Default")
      (node (ref "U13") (pin "M19") (pinfunction "IO,_DIFFIO_R27p,_(_)/(DQ1R)/(DQ1R)_M19") (pintype "bidirectional"))
    )
    (net (code "175") (name "/M20") (class "Default")
      (node (ref "U13") (pin "M20") (pinfunction "IO,_DIFFIO_R27n,_(DM0R)/(DM1R/BWS#1R)/(DM1R/BWS#1R)_M20") (pintype "bidirectional"))
    )
    (net (code "176") (name "/M21") (class "Default")
      (node (ref "U13") (pin "M21") (pinfunction "IO,_DIFFIO_R28p_M21") (pintype "bidirectional"))
    )
    (net (code "177") (name "/M22") (class "Default")
      (node (ref "U13") (pin "M22") (pinfunction "IO,_DIFFIO_R28n,_(DQ1R)/(DQ3R)/(DQ1R)_M22") (pintype "bidirectional"))
    )
    (net (code "178") (name "/N1") (class "Default")
      (node (ref "U13") (pin "N1") (pinfunction "IO,_DIFFIO_L29n_N1") (pintype "bidirectional"))
    )
    (net (code "179") (name "/N2") (class "Default")
      (node (ref "U13") (pin "N2") (pinfunction "IO,_DIFFIO_L29p,_(DQ1L)/(DQ3L)/(DQ1L)_N2") (pintype "bidirectional"))
    )
    (net (code "180") (name "/N5") (class "Default")
      (node (ref "U13") (pin "N5") (pinfunction "IO,_DIFFIO_L32n,_(DQ1L)/(DQ3L)/(DQ1L)_N5") (pintype "bidirectional"))
    )
    (net (code "181") (name "/N6") (class "Default")
      (node (ref "U13") (pin "N6") (pinfunction "IO,_DIFFIO_L36n_N6") (pintype "bidirectional"))
    )
    (net (code "182") (name "/N18") (class "Default")
      (node (ref "U13") (pin "N18") (pinfunction "IO,_DIFFIO_R30p,_(DQS1R/CQ1R#,DPCLK6)/(DQS1R/CQ1R#,DPCLK6)/(DQS1R/CQ1R#,DPCLK6)_N18") (pintype "bidirectional"))
    )
    (net (code "183") (name "/N19") (class "Default")
      (node (ref "U13") (pin "N19") (pinfunction "IO,_VREFB5N0_N19") (pintype "bidirectional"))
    )
    (net (code "184") (name "/N20") (class "Default")
      (node (ref "U13") (pin "N20") (pinfunction "IO,_DIFFIO_R33n_N20") (pintype "bidirectional"))
    )
    (net (code "185") (name "/N21") (class "Default")
      (node (ref "U13") (pin "N21") (pinfunction "IO,_DIFFIO_R29p,_(DEV_CLRn)_N21") (pintype "bidirectional"))
    )
    (net (code "186") (name "/N22") (class "Default")
      (node (ref "U13") (pin "N22") (pinfunction "IO,_DIFFIO_R29n,_(DEV_OE)_N22") (pintype "bidirectional"))
    )
    (net (code "187") (name "/P1") (class "Default")
      (node (ref "U13") (pin "P1") (pinfunction "IO,_DIFFIO_L30n,_(DQ1L)/(DQ3L)/(DQ1L)_P1") (pintype "bidirectional"))
    )
    (net (code "188") (name "/P2") (class "Default")
      (node (ref "U13") (pin "P2") (pinfunction "IO,_DIFFIO_L30p_P2") (pintype "bidirectional"))
    )
    (net (code "189") (name "/P3") (class "Default")
      (node (ref "U13") (pin "P3") (pinfunction "IO,_DIFFIO_L33n_P3") (pintype "bidirectional"))
    )
    (net (code "190") (name "/P4") (class "Default")
      (node (ref "U13") (pin "P4") (pinfunction "IO,_DIFFIO_L33p,_(DQS1L/CQ1L#,DPCLK1)/(DQS1L/CQ1L#,DPCLK1)/(DQS1L/CQ1L#,DPCLK1)_P4") (pintype "bidirectional"))
    )
    (net (code "191") (name "/P5") (class "Default")
      (node (ref "U13") (pin "P5") (pinfunction "IO,_DIFFIO_L36p,_(DQ3L)/(DQ3L)/(DQ1L)_P5") (pintype "bidirectional"))
    )
    (net (code "192") (name "/P20") (class "Default")
      (node (ref "U13") (pin "P20") (pinfunction "IO,_VREFB5N1_P20") (pintype "bidirectional"))
    )
    (net (code "193") (name "/P21") (class "Default")
      (node (ref "U13") (pin "P21") (pinfunction "IO,_DIFFIO_R36p_P21") (pintype "bidirectional"))
    )
    (net (code "194") (name "/P22") (class "Default")
      (node (ref "U13") (pin "P22") (pinfunction "IO,_DIFFIO_R36n_P22") (pintype "bidirectional"))
    )
    (net (code "195") (name "/R1") (class "Default")
      (node (ref "U13") (pin "R1") (pinfunction "IO,_DIFFIO_L31n_R1") (pintype "bidirectional"))
    )
    (net (code "196") (name "/R2") (class "Default")
      (node (ref "U13") (pin "R2") (pinfunction "IO,_DIFFIO_L31p,_(DQ1L)/(DQ3L)/(DQ1L)_R2") (pintype "bidirectional"))
    )
    (net (code "197") (name "/R3") (class "Default")
      (node (ref "U13") (pin "R3") (pinfunction "IO,_DIFFIO_L37n,_(DQ3L)/(DQ3L)/(DQ1L)_R3") (pintype "bidirectional"))
    )
    (net (code "198") (name "/R4") (class "Default")
      (node (ref "U13") (pin "R4") (pinfunction "IO,_DIFFIO_L37p,_(DQ3L)/(DQ3L)/(DQ1L)_R4") (pintype "bidirectional"))
    )
    (net (code "199") (name "/R5") (class "Default")
      (node (ref "U13") (pin "R5") (pinfunction "IO,_VREFB2N2_R5") (pintype "bidirectional"))
    )
    (net (code "200") (name "/R16") (class "Default")
      (node (ref "U13") (pin "R16") (pinfunction "IO,_PLL4_CLKOUTn_R16") (pintype "bidirectional"))
    )
    (net (code "201") (name "/R17") (class "Default")
      (node (ref "U13") (pin "R17") (pinfunction "IO,_DIFFIO_R49p_R17") (pintype "bidirectional"))
    )
    (net (code "202") (name "/R19") (class "Default")
      (node (ref "U13") (pin "R19") (pinfunction "IO,_DIFFIO_R40p_R19") (pintype "bidirectional"))
    )
    (net (code "203") (name "/R20") (class "Default")
      (node (ref "U13") (pin "R20") (pinfunction "IO,_DIFFIO_R42n,_(DM1R/BWS#1R)/(DM3R/BWS#3R)/(DM1R/BWS#1R)_R20") (pintype "bidirectional"))
    )
    (net (code "204") (name "/R21") (class "Default")
      (node (ref "U13") (pin "R21") (pinfunction "IO,_DIFFIO_R38p_R21") (pintype "bidirectional"))
    )
    (net (code "205") (name "/R22") (class "Default")
      (node (ref "U13") (pin "R22") (pinfunction "IO,_DIFFIO_R38n,_(DQ1R)/(DQ3R)/(DQ1R)_R22") (pintype "bidirectional"))
    )
    (net (code "206") (name "/T3") (class "Default")
      (node (ref "U13") (pin "T3") (pinfunction "IO,_VREFB2N1_T3") (pintype "bidirectional"))
    )
    (net (code "207") (name "/T4") (class "Default")
      (node (ref "U13") (pin "T4") (pinfunction "IO,_DIFFIO_L48p,_(DQS3L/CQ3L#,CDPCLK1)/(DQS3L/CQ3L#,CDPCLK1)/(DQS3L/CQ3L#,CDPCLK1)_T4") (pintype "bidirectional"))
    )
    (net (code "208") (name "/T5") (class "Default")
      (node (ref "U13") (pin "T5") (pinfunction "IO,_DIFFIO_L48n,_(DM3L/BWS#3L)/(DM3L/BWS#3L)/(DM1L/BWS#1L)_T5") (pintype "bidirectional"))
    )
    (net (code "209") (name "/T15") (class "Default")
      (node (ref "U13") (pin "T15") (pinfunction "IO,_DIFFIO_B46n,_(DQ0B)/(_)/(_)_T15") (pintype "bidirectional"))
    )
    (net (code "210") (name "/T16") (class "Default")
      (node (ref "U13") (pin "T16") (pinfunction "IO,_PLL4_CLKOUTp_T16") (pintype "bidirectional"))
    )
    (net (code "211") (name "/T17") (class "Default")
      (node (ref "U13") (pin "T17") (pinfunction "IO,_RUP3_T17") (pintype "bidirectional"))
    )
    (net (code "212") (name "/T18") (class "Default")
      (node (ref "U13") (pin "T18") (pinfunction "IO,_RDN3_T18") (pintype "bidirectional"))
    )
    (net (code "213") (name "/T19") (class "Default")
      (node (ref "U13") (pin "T19") (pinfunction "IO,_DIFFIO_R45p,_(DQ3R)/(DQ3R)/(DQ1R)_T19") (pintype "bidirectional"))
    )
    (net (code "214") (name "/T20") (class "Default")
      (node (ref "U13") (pin "T20") (pinfunction "IO,_DIFFIO_R45n,_(DQ3R)/(DQ3R)/(DQ1R)_T20") (pintype "bidirectional"))
    )
    (net (code "215") (name "/TCK") (class "Default")
      (node (ref "JP6") (pin "1") (pinfunction "1_1") (pintype "passive"))
      (node (ref "R46") (pin "2") (pinfunction "2_2") (pintype "passive"))
      (node (ref "U13") (pin "L2") (pinfunction "TCK_L2") (pintype "input"))
    )
    (net (code "216") (name "/TDI") (class "Default")
      (node (ref "JP6") (pin "9") (pinfunction "9_9") (pintype "passive"))
      (node (ref "R51") (pin "2") (pinfunction "2_2") (pintype "passive"))
      (node (ref "U13") (pin "L5") (pinfunction "TDI_L5") (pintype "input"))
    )
    (net (code "217") (name "/TDO") (class "Default")
      (node (ref "JP6") (pin "3") (pinfunction "3_3") (pintype "passive"))
      (node (ref "U13") (pin "L4") (pinfunction "TDO_L4") (pintype "output"))
    )
    (net (code "218") (name "/TMS") (class "Default")
      (node (ref "JP6") (pin "5") (pinfunction "5_5") (pintype "passive"))
      (node (ref "R50") (pin "2") (pinfunction "2_2") (pintype "passive"))
      (node (ref "U13") (pin "L1") (pinfunction "TMS_L1") (pintype "input"))
    )
    (net (code "219") (name "/U1") (class "Default")
      (node (ref "U13") (pin "U1") (pinfunction "IO,_DIFFIO_L34n,_(DM1L/BWS#1L)/(DM3L/BWS#3L)/(DM1L/BWS#1L)_U1") (pintype "bidirectional"))
    )
    (net (code "220") (name "/U2") (class "Default")
      (node (ref "U13") (pin "U2") (pinfunction "IO,_DIFFIO_L34p,_(DQ1L)/(DQ3L)/(DQ1L)_U2") (pintype "bidirectional"))
    )
    (net (code "221") (name "/U9") (class "Default")
      (node (ref "U13") (pin "U9") (pinfunction "IO,_DIFFIO_B12n,_(DQ3B)/(DQ3B)/(DQ5B)_U9") (pintype "bidirectional"))
    )
    (net (code "222") (name "/U10") (class "Default")
      (node (ref "U13") (pin "U10") (pinfunction "IO,_DIFFIO_B15n,_(DQ5B)/(DQ3B)/(DQ5B)_U10") (pintype "bidirectional"))
    )
    (net (code "223") (name "/U11") (class "Default")
      (node (ref "U13") (pin "U11") (pinfunction "IO,_VREFB3N0_U11") (pintype "bidirectional"))
    )
    (net (code "224") (name "/U12") (class "Default")
      (node (ref "U13") (pin "U12") (pinfunction "IO,_DIFFIO_B38p_U12") (pintype "bidirectional"))
    )
    (net (code "225") (name "/U14") (class "Default")
      (node (ref "U13") (pin "U14") (pinfunction "IO,_DIFFIO_B44p,_(DQ2B)/(DQ5B)/(DQ5B)_U14") (pintype "bidirectional"))
    )
    (net (code "226") (name "/U20") (class "Default")
      (node (ref "U13") (pin "U20") (pinfunction "IO,_DIFFIO_R48n,_(DQ3R)/(DQ3R)/(DQ1R)_U20") (pintype "bidirectional"))
    )
    (net (code "227") (name "/U21") (class "Default")
      (node (ref "U13") (pin "U21") (pinfunction "IO,_DIFFIO_R41p_U21") (pintype "bidirectional"))
    )
    (net (code "228") (name "/U22") (class "Default")
      (node (ref "U13") (pin "U22") (pinfunction "IO,_DIFFIO_R41n,_(DQ1R)/(DQ3R)/(DQ1R)_U22") (pintype "bidirectional"))
    )
    (net (code "229") (name "/V1") (class "Default")
      (node (ref "U13") (pin "V1") (pinfunction "IO,_DIFFIO_L35n_V1") (pintype "bidirectional"))
    )
    (net (code "230") (name "/V2") (class "Default")
      (node (ref "U13") (pin "V2") (pinfunction "IO,_DIFFIO_L35p,_(DQ3L)/(DQ3L)/(DQ1L)_V2") (pintype "bidirectional"))
    )
    (net (code "231") (name "/V3") (class "Default")
      (node (ref "U13") (pin "V3") (pinfunction "IO,_RDN1_V3") (pintype "bidirectional"))
    )
    (net (code "232") (name "/V4") (class "Default")
      (node (ref "U13") (pin "V4") (pinfunction "IO,_RUP1_V4") (pintype "bidirectional"))
    )
    (net (code "233") (name "/V5") (class "Default")
      (node (ref "U13") (pin "V5") (pinfunction "IO,_DIFFIO_B1n,_(DM1B)/(_)/(_)_V5") (pintype "bidirectional"))
    )
    (net (code "234") (name "/V8") (class "Default")
      (node (ref "U13") (pin "V8") (pinfunction "IO,_DIFFIO_B13p_V8") (pintype "bidirectional"))
    )
    (net (code "235") (name "/V9") (class "Default")
      (node (ref "U13") (pin "V9") (pinfunction "IO,_VREFB3N1_V9") (pintype "bidirectional"))
    )
    (net (code "236") (name "/V10") (class "Default")
      (node (ref "U13") (pin "V10") (pinfunction "IO,_DIFFIO_B15p,_(DQS3B/CQ3B#,DPCLK2)/(DQS3B/CQ3B#,DPCLK2)/(DQS3B/CQ3B#,DPCLK2)_V10") (pintype "bidirectional"))
    )
    (net (code "237") (name "/V11") (class "Default")
      (node (ref "U13") (pin "V11") (pinfunction "IO_V11") (pintype "bidirectional"))
    )
    (net (code "238") (name "/V12") (class "Default")
      (node (ref "U13") (pin "V12") (pinfunction "IO,_VREFB4N2_V12") (pintype "bidirectional"))
    )
    (net (code "239") (name "/V13") (class "Default")
      (node (ref "U13") (pin "V13") (pinfunction "IO,_DIFFIO_B41p,_(DQS2B/CQ3B,DPCLK5)/(DQS2B/CQ3B,DPCLK5)/(DQS2B/CQ3B,DPCLK5)_V13") (pintype "bidirectional"))
    )
    (net (code "240") (name "/V14") (class "Default")
      (node (ref "U13") (pin "V14") (pinfunction "IO,_DIFFIO_B43p_V14") (pintype "bidirectional"))
    )
    (net (code "241") (name "/V15") (class "Default")
      (node (ref "U13") (pin "V15") (pinfunction "IO,_DIFFIO_B44n_V15") (pintype "bidirectional"))
    )
    (net (code "242") (name "/V16") (class "Default")
      (node (ref "U13") (pin "V16") (pinfunction "IO,_VREFB4N0_V16") (pintype "bidirectional"))
    )
    (net (code "243") (name "/V21") (class "Default")
      (node (ref "U13") (pin "V21") (pinfunction "IO,_DIFFIO_R43p_V21") (pintype "bidirectional"))
    )
    (net (code "244") (name "/V22") (class "Default")
      (node (ref "U13") (pin "V22") (pinfunction "IO,_DIFFIO_R43n,_(DQ3R)/(DQ3R)/(DQ1R)_V22") (pintype "bidirectional"))
    )
    (net (code "245") (name "/W1") (class "Default")
      (node (ref "U13") (pin "W1") (pinfunction "IO,_DIFFIO_L38n_W1") (pintype "bidirectional"))
    )
    (net (code "246") (name "/W2") (class "Default")
      (node (ref "U13") (pin "W2") (pinfunction "IO,_DIFFIO_L38p,_(DQ3L)/(DQ3L)/(DQ1L)_W2") (pintype "bidirectional"))
    )
    (net (code "247") (name "/W6") (class "Default")
      (node (ref "U13") (pin "W6") (pinfunction "IO,_DIFFIO_B4p,_(DQ1B)/(_)/(_)_W6") (pintype "bidirectional"))
    )
    (net (code "248") (name "/W7") (class "Default")
      (node (ref "U13") (pin "W7") (pinfunction "IO,_DIFFIO_B9p,_(DQ3B)/(DQ3B)/(DQ5B)_W7") (pintype "bidirectional"))
    )
    (net (code "249") (name "/W8") (class "Default")
      (node (ref "U13") (pin "W8") (pinfunction "IO,_DIFFIO_B13n,_(DQ3B)/(DQ3B)/(DQ5B)_W8") (pintype "bidirectional"))
    )
    (net (code "250") (name "/W10") (class "Default")
      (node (ref "U13") (pin "W10") (pinfunction "IO,_DIFFIO_B23p_W10") (pintype "bidirectional"))
    )
    (net (code "251") (name "/W13") (class "Default")
      (node (ref "U13") (pin "W13") (pinfunction "IO,_DIFFIO_B36p,_(DQ4B)/(DQ5B)/(DQ5B)_W13") (pintype "bidirectional"))
    )
    (net (code "252") (name "/W14") (class "Default")
      (node (ref "U13") (pin "W14") (pinfunction "IO,_DIFFIO_B41n_W14") (pintype "bidirectional"))
    )
    (net (code "253") (name "/W15") (class "Default")
      (node (ref "U13") (pin "W15") (pinfunction "IO,_DIFFIO_B45p,_(DQ2B)/(DQ5B)/(DQ5B)_W15") (pintype "bidirectional"))
    )
    (net (code "254") (name "/W17") (class "Default")
      (node (ref "U13") (pin "W17") (pinfunction "IO,_DIFFIO_B48p,_(DQ0B)/(_)/(_)_W17") (pintype "bidirectional"))
    )
    (net (code "255") (name "/W19") (class "Default")
      (node (ref "U13") (pin "W19") (pinfunction "IO,_VREFB5N2_W19") (pintype "bidirectional"))
    )
    (net (code "256") (name "/W20") (class "Default")
      (node (ref "U13") (pin "W20") (pinfunction "IO,_DIFFIO_R50n,_(DQS3R/CQ3R#,CDPCLK4)/(DQS3R/CQ3R#,CDPCLK4)/(DQS3R/CQ3R#,CDPCLK4)_W20") (pintype "bidirectional"))
    )
    (net (code "257") (name "/W21") (class "Default")
      (node (ref "U13") (pin "W21") (pinfunction "IO,_DIFFIO_R46p_W21") (pintype "bidirectional"))
    )
    (net (code "258") (name "/W22") (class "Default")
      (node (ref "U13") (pin "W22") (pinfunction "IO,_DIFFIO_R46n,_(DQ3R)/(DQ3R)/(DQ1R)_W22") (pintype "bidirectional"))
    )
    (net (code "259") (name "/Y1") (class "Default")
      (node (ref "U13") (pin "Y1") (pinfunction "IO,_DIFFIO_L39n_Y1") (pintype "bidirectional"))
    )
    (net (code "260") (name "/Y2") (class "Default")
      (node (ref "U13") (pin "Y2") (pinfunction "IO,_DIFFIO_L39p,_(DQ3L)/(DQ3L)/(DQ1L)_Y2") (pintype "bidirectional"))
    )
    (net (code "261") (name "/Y3") (class "Default")
      (node (ref "U13") (pin "Y3") (pinfunction "IO,_DIFFIO_B3n,_(DQ1B)/(_)/(_)_Y3") (pintype "bidirectional"))
    )
    (net (code "262") (name "/Y4") (class "Default")
      (node (ref "U13") (pin "Y4") (pinfunction "IO,_DIFFIO_B3p_Y4") (pintype "bidirectional"))
    )
    (net (code "263") (name "/Y6") (class "Default")
      (node (ref "U13") (pin "Y6") (pinfunction "IO,_(DQS1B/CQ1B#,CDPCLK2)/(DQS1B/CQ1B#,CDPCLK2)/(DQS1B/CQ1B#,CDPCLK2)_Y6") (pintype "bidirectional"))
    )
    (net (code "264") (name "/Y7") (class "Default")
      (node (ref "U13") (pin "Y7") (pinfunction "IO,_DIFFIO_B9n,_(DQ3B)/(DQ3B)/(DQ5B)_Y7") (pintype "bidirectional"))
    )
    (net (code "265") (name "/Y8") (class "Default")
      (node (ref "U13") (pin "Y8") (pinfunction "IO,_(DQ5B)/(DQ3B)/(DQ5B)_Y8") (pintype "bidirectional"))
    )
    (net (code "266") (name "/Y10") (class "Default")
      (node (ref "U13") (pin "Y10") (pinfunction "IO,_DIFFIO_B23n_Y10") (pintype "bidirectional"))
    )
    (net (code "267") (name "/Y13") (class "Default")
      (node (ref "U13") (pin "Y13") (pinfunction "IO,_DIFFIO_B36n,_(DQS4B/CQ5B,DPCLK4)/(DQS4B/CQ5B,DPCLK4)/(DQS4B/CQ5B,DPCLK4)_Y13") (pintype "bidirectional"))
    )
    (net (code "268") (name "/Y14") (class "Default")
      (node (ref "U13") (pin "Y14") (pinfunction "IO,_DIFFIO_B39p_Y14") (pintype "bidirectional"))
    )
    (net (code "269") (name "/Y15") (class "Default")
      (node (ref "U13") (pin "Y15") (pinfunction "IO,_DIFFIO_B39n,_(DQ2B)/(DQ5B)/(DQ5B)_Y15") (pintype "bidirectional"))
    )
    (net (code "270") (name "/Y17") (class "Default")
      (node (ref "U13") (pin "Y17") (pinfunction "IO,_DIFFIO_B48n,_(DQS0B/CQ1B,CDPCLK3)/(DQS0B/CQ1B,CDPCLK3)/(DQS0B/CQ1B,CDPCLK3)_Y17") (pintype "bidirectional"))
    )
    (net (code "271") (name "/Y22") (class "Default")
      (node (ref "U13") (pin "Y22") (pinfunction "IO,_DIFFIO_R49n,_(DQ3R)/(DQ3R)/(DQ1R)_Y22") (pintype "bidirectional"))
    )
    (net (code "272") (name "/nCONFIG") (class "Default")
      (node (ref "R55") (pin "1") (pinfunction "1_1") (pintype "passive"))
      (node (ref "U13") (pin "K5") (pinfunction "nCONFIG_K5") (pintype "input"))
    )
    (net (code "273") (name "/nCSO") (class "Default")
      (node (ref "R48") (pin "2") (pinfunction "2_2") (pintype "passive"))
      (node (ref "U13") (pin "E2") (pinfunction "IO,_DIFFIO_L8p,_(FLASH_nCE,nCSO)_E2") (pintype "bidirectional"))
      (node (ref "U14") (pin "1") (pinfunction "~{CS}_1") (pintype "passive"))
    )
    (net (code "274") (name "/nSTATUS") (class "Default")
      (node (ref "R56") (pin "1") (pinfunction "1_1") (pintype "passive"))
      (node (ref "U13") (pin "K6") (pinfunction "nSTATUS_K6") (pintype "bidirectional"))
    )
    (net (code "275") (name "1V2") (class "Default")
      (node (ref "C100") (pin "2") (pinfunction "2_2") (pintype "passive"))
      (node (ref "C101") (pin "2") (pinfunction "2_2") (pintype "passive"))
      (node (ref "C102") (pin "2") (pinfunction "2_2") (pintype "passive"))
      (node (ref "C104") (pin "2") (pinfunction "2_2") (pintype "passive"))
      (node (ref "C105") (pin "2") (pinfunction "2_2") (pintype "passive"))
      (node (ref "C106") (pin "2") (pinfunction "2_2") (pintype "passive"))
      (node (ref "C107") (pin "2") (pinfunction "2_2") (pintype "passive"))
      (node (ref "C108") (pin "2") (pinfunction "2_2") (pintype "passive"))
      (node (ref "C109") (pin "2") (pinfunction "2_2") (pintype "passive"))
      (node (ref "C110") (pin "2") (pinfunction "2_2") (pintype "passive"))
      (node (ref "C111") (pin "2") (pinfunction "2_2") (pintype "passive"))
      (node (ref "C112") (pin "2") (pinfunction "2_2") (pintype "passive"))
      (node (ref "C113") (pin "2") (pinfunction "2_2") (pintype "passive"))
      (node (ref "C114") (pin "2") (pinfunction "2_2") (pintype "passive"))
      (node (ref "C115") (pin "2") (pinfunction "2_2") (pintype "passive"))
      (node (ref "C117") (pin "2") (pinfunction "2_2") (pintype "passive"))
      (node (ref "C118") (pin "2") (pinfunction "2_2") (pintype "passive"))
      (node (ref "C119") (pin "2") (pinfunction "2_2") (pintype "passive"))
      (node (ref "C147") (pin "2") (pinfunction "2_2") (pintype "passive"))
      (node (ref "C87") (pin "2") (pinfunction "2_2") (pintype "passive"))
      (node (ref "C88") (pin "2") (pinfunction "2_2") (pintype "passive"))
      (node (ref "C89") (pin "2") (pinfunction "2_2") (pintype "passive"))
      (node (ref "C90") (pin "2") (pinfunction "2_2") (pintype "passive"))
      (node (ref "C91") (pin "2") (pinfunction "2_2") (pintype "passive"))
      (node (ref "C92") (pin "2") (pinfunction "2_2") (pintype "passive"))
      (node (ref "C93") (pin "2") (pinfunction "2_2") (pintype "passive"))
      (node (ref "C94") (pin "2") (pinfunction "2_2") (pintype "passive"))
      (node (ref "C95") (pin "2") (pinfunction "2_2") (pintype "passive"))
      (node (ref "C96") (pin "2") (pinfunction "2_2") (pintype "passive"))
      (node (ref "C97") (pin "2") (pinfunction "2_2") (pintype "passive"))
      (node (ref "C98") (pin "2") (pinfunction "2_2") (pintype "passive"))
      (node (ref "C99") (pin "2") (pinfunction "2_2") (pintype "passive"))
      (node (ref "U13") (pin "E17") (pinfunction "VCCD_PLL2_E17") (pintype "power_in"))
      (node (ref "U13") (pin "F6") (pinfunction "VCCD_PLL3_F6") (pintype "power_in"))
      (node (ref "U13") (pin "G10") (pinfunction "VCCINT_G10") (pintype "power_in"))
      (node (ref "U13") (pin "G12") (pinfunction "VCCINT_G12") (pintype "power_in"))
      (node (ref "U13") (pin "G14") (pinfunction "VCCINT_G14") (pintype "power_in"))
      (node (ref "U13") (pin "G16") (pinfunction "VCCINT_G16") (pintype "power_in"))
      (node (ref "U13") (pin "G4") (pinfunction "VCCINT_G4") (pintype "power_in"))
      (node (ref "U13") (pin "G8") (pinfunction "VCCINT_G8") (pintype "power_in"))
      (node (ref "U13") (pin "H11") (pinfunction "VCCINT_H11") (pintype "power_in"))
      (node (ref "U13") (pin "H15") (pinfunction "VCCINT_H15") (pintype "power_in"))
      (node (ref "U13") (pin "H17") (pinfunction "VCCINT_H17") (pintype "power_in"))
      (node (ref "U13") (pin "H9") (pinfunction "VCCINT_H9") (pintype "power_in"))
      (node (ref "U13") (pin "J10") (pinfunction "VCCINT_J10") (pintype "power_in"))
      (node (ref "U13") (pin "J11") (pinfunction "VCCINT_J11") (pintype "power_in"))
      (node (ref "U13") (pin "J12") (pinfunction "VCCINT_J12") (pintype "power_in"))
      (node (ref "U13") (pin "J13") (pinfunction "VCCINT_J13") (pintype "power_in"))
      (node (ref "U13") (pin "J14") (pinfunction "VCCINT_J14") (pintype "power_in"))
      (node (ref "U13") (pin "J16") (pinfunction "VCCINT_J16") (pintype "power_in"))
      (node (ref "U13") (pin "J17") (pinfunction "VCCINT_J17") (pintype "power_in"))
      (node (ref "U13") (pin "J7") (pinfunction "VCCINT_J7") (pintype "power_in"))
      (node (ref "U13") (pin "J8") (pinfunction "VCCINT_J8") (pintype "power_in"))
      (node (ref "U13") (pin "K14") (pinfunction "VCCINT_K14") (pintype "power_in"))
      (node (ref "U13") (pin "K15") (pinfunction "VCCINT_K15") (pintype "power_in"))
      (node (ref "U13") (pin "K17") (pinfunction "VCCINT_K17") (pintype "power_in"))
      (node (ref "U13") (pin "K8") (pinfunction "VCCINT_K8") (pintype "power_in"))
      (node (ref "U13") (pin "K9") (pinfunction "VCCINT_K9") (pintype "power_in"))
      (node (ref "U13") (pin "L14") (pinfunction "VCCINT_L14") (pintype "power_in"))
      (node (ref "U13") (pin "L16") (pinfunction "VCCINT_L16") (pintype "power_in"))
      (node (ref "U13") (pin "L7") (pinfunction "VCCINT_L7") (pintype "power_in"))
      (node (ref "U13") (pin "L9") (pinfunction "VCCINT_L9") (pintype "power_in"))
      (node (ref "U13") (pin "M14") (pinfunction "VCCINT_M14") (pintype "power_in"))
      (node (ref "U13") (pin "M15") (pinfunction "VCCINT_M15") (pintype "power_in"))
      (node (ref "U13") (pin "M8") (pinfunction "VCCINT_M8") (pintype "power_in"))
      (node (ref "U13") (pin "M9") (pinfunction "VCCINT_M9") (pintype "power_in"))
      (node (ref "U13") (pin "N14") (pinfunction "VCCINT_N14") (pintype "power_in"))
      (node (ref "U13") (pin "N16") (pinfunction "VCCINT_N16") (pintype "power_in"))
      (node (ref "U13") (pin "N7") (pinfunction "VCCINT_N7") (pintype "power_in"))
      (node (ref "U13") (pin "N9") (pinfunction "VCCINT_N9") (pintype "power_in"))
      (node (ref "U13") (pin "P10") (pinfunction "VCCINT_P10") (pintype "power_in"))
      (node (ref "U13") (pin "P11") (pinfunction "VCCINT_P11") (pintype "power_in"))
      (node (ref "U13") (pin "P12") (pinfunction "VCCINT_P12") (pintype "power_in"))
      (node (ref "U13") (pin "P13") (pinfunction "VCCINT_P13") (pintype "power_in"))
      (node (ref "U13") (pin "P14") (pinfunction "VCCINT_P14") (pintype "power_in"))
      (node (ref "U13") (pin "P15") (pinfunction "VCCINT_P15") (pintype "power_in"))
      (node (ref "U13") (pin "P17") (pinfunction "VCCINT_P17") (pintype "power_in"))
      (node (ref "U13") (pin "P7") (pinfunction "VCCINT_P7") (pintype "power_in"))
      (node (ref "U13") (pin "P9") (pinfunction "VCCINT_P9") (pintype "power_in"))
      (node (ref "U13") (pin "R10") (pinfunction "VCCINT_R10") (pintype "power_in"))
      (node (ref "U13") (pin "R12") (pinfunction "VCCINT_R12") (pintype "power_in"))
      (node (ref "U13") (pin "R14") (pinfunction "VCCINT_R14") (pintype "power_in"))
      (node (ref "U13") (pin "R15") (pinfunction "VCCINT_R15") (pintype "power_in"))
      (node (ref "U13") (pin "R6") (pinfunction "VCCINT_R6") (pintype "power_in"))
      (node (ref "U13") (pin "R8") (pinfunction "VCCINT_R8") (pintype "power_in"))
      (node (ref "U13") (pin "T11") (pinfunction "VCCINT_T11") (pintype "power_in"))
      (node (ref "U13") (pin "T13") (pinfunction "VCCINT_T13") (pintype "power_in"))
      (node (ref "U13") (pin "T7") (pinfunction "VCCINT_T7") (pintype "power_in"))
      (node (ref "U13") (pin "T9") (pinfunction "VCCINT_T9") (pintype "power_in"))
      (node (ref "U13") (pin "U15") (pinfunction "VCCINT_U15") (pintype "power_in"))
      (node (ref "U13") (pin "U16") (pinfunction "VCCINT_U16") (pintype "power_in"))
      (node (ref "U13") (pin "U17") (pinfunction "VCCINT_U17") (pintype "power_in"))
      (node (ref "U13") (pin "U6") (pinfunction "VCCD_PLL1_U6") (pintype "power_in"))
      (node (ref "U13") (pin "U8") (pinfunction "VCCINT_U8") (pintype "power_in"))
      (node (ref "U13") (pin "V17") (pinfunction "VCCD_PLL4_V17") (pintype "power_in"))
      (node (ref "U13") (pin "V7") (pinfunction "VCCINT_V7") (pintype "power_in"))
    )
    (net (code "276") (name "2V5") (class "Default")
      (node (ref "C122") (pin "2") (pinfunction "2_2") (pintype "passive"))
      (node (ref "C123") (pin "2") (pinfunction "2_2") (pintype "passive"))
      (node (ref "C124") (pin "2") (pinfunction "2_2") (pintype "passive"))
      (node (ref "C125") (pin "2") (pinfunction "2_2") (pintype "passive"))
      (node (ref "U13") (pin "F18") (pinfunction "VCCA2_F18") (pintype "power_in"))
      (node (ref "U13") (pin "G6") (pinfunction "VCCA3_G6") (pintype "power_in"))
      (node (ref "U13") (pin "L18") (pinfunction "MSEL1_L18") (pintype "input"))
      (node (ref "U13") (pin "T6") (pinfunction "VCCA1_T6") (pintype "power_in"))
      (node (ref "U13") (pin "U18") (pinfunction "VCCA4_U18") (pintype "power_in"))
    )
    (net (code "277") (name "3V3") (class "Default")
      (node (ref "C103") (pin "1") (pinfunction "1_1") (pintype "passive"))
      (node (ref "C120") (pin "1") (pinfunction "1_1") (pintype "passive"))
      (node (ref "C58") (pin "2") (pinfunction "2_2") (pintype "passive"))
      (node (ref "C59") (pin "2") (pinfunction "2_2") (pintype "passive"))
      (node (ref "C60") (pin "2") (pinfunction "2_2") (pintype "passive"))
      (node (ref "C61") (pin "2") (pinfunction "2_2") (pintype "passive"))
      (node (ref "C62") (pin "2") (pinfunction "2_2") (pintype "passive"))
      (node (ref "C63") (pin "2") (pinfunction "2_2") (pintype "passive"))
      (node (ref "C64") (pin "2") (pinfunction "2_2") (pintype "passive"))
      (node (ref "C65") (pin "2") (pinfunction "2_2") (pintype "passive"))
      (node (ref "C66") (pin "2") (pinfunction "2_2") (pintype "passive"))
      (node (ref "C67") (pin "2") (pinfunction "2_2") (pintype "passive"))
      (node (ref "C68") (pin "2") (pinfunction "2_2") (pintype "passive"))
      (node (ref "C69") (pin "2") (pinfunction "2_2") (pintype "passive"))
      (node (ref "C70") (pin "2") (pinfunction "2_2") (pintype "passive"))
      (node (ref "C71") (pin "2") (pinfunction "2_2") (pintype "passive"))
      (node (ref "C72") (pin "2") (pinfunction "2_2") (pintype "passive"))
      (node (ref "C73") (pin "2") (pinfunction "2_2") (pintype "passive"))
      (node (ref "C74") (pin "2") (pinfunction "2_2") (pintype "passive"))
      (node (ref "C75") (pin "2") (pinfunction "2_2") (pintype "passive"))
      (node (ref "C76") (pin "2") (pinfunction "2_2") (pintype "passive"))
      (node (ref "C77") (pin "2") (pinfunction "2_2") (pintype "passive"))
      (node (ref "C78") (pin "2") (pinfunction "2_2") (pintype "passive"))
      (node (ref "C79") (pin "2") (pinfunction "2_2") (pintype "passive"))
      (node (ref "C80") (pin "2") (pinfunction "2_2") (pintype "passive"))
      (node (ref "C81") (pin "2") (pinfunction "2_2") (pintype "passive"))
      (node (ref "C82") (pin "2") (pinfunction "2_2") (pintype "passive"))
      (node (ref "C83") (pin "2") (pinfunction "2_2") (pintype "passive"))
      (node (ref "C84") (pin "2") (pinfunction "2_2") (pintype "passive"))
      (node (ref "C85") (pin "2") (pinfunction "2_2") (pintype "passive"))
      (node (ref "C86") (pin "2") (pinfunction "2_2") (pintype "passive"))
      (node (ref "FB2") (pin "1") (pinfunction "1_1") (pintype "passive"))
      (node (ref "JP6") (pin "4") (pinfunction "4_4") (pintype "passive"))
      (node (ref "JP6") (pin "6") (pinfunction "6_6") (pintype "passive"))
      (node (ref "R45") (pin "1") (pinfunction "1_1") (pintype "passive"))
      (node (ref "R47") (pin "1") (pinfunction "1_1") (pintype "passive"))
      (node (ref "R48") (pin "1") (pinfunction "1_1") (pintype "passive"))
      (node (ref "R49") (pin "2") (pinfunction "2_2") (pintype "passive"))
      (node (ref "R50") (pin "1") (pinfunction "1_1") (pintype "passive"))
      (node (ref "R51") (pin "1") (pinfunction "1_1") (pintype "passive"))
      (node (ref "R54") (pin "2") (pinfunction "2_2") (pintype "passive"))
      (node (ref "R55") (pin "2") (pinfunction "2_2") (pintype "passive"))
      (node (ref "R56") (pin "2") (pinfunction "2_2") (pintype "passive"))
      (node (ref "U13") (pin "A2") (pinfunction "VCCIO8_A2") (pintype "power_in"))
      (node (ref "U13") (pin "A21") (pinfunction "VCCIO7_A21") (pintype "power_in"))
      (node (ref "U13") (pin "AB2") (pinfunction "VCCIO3_AB2") (pintype "power_in"))
      (node (ref "U13") (pin "AB21") (pinfunction "VCCIO4_AB21") (pintype "power_in"))
      (node (ref "U13") (pin "D11") (pinfunction "VCCIO8_D11") (pintype "power_in"))
      (node (ref "U13") (pin "D12") (pinfunction "VCCIO7_D12") (pintype "power_in"))
      (node (ref "U13") (pin "D14") (pinfunction "VCCIO7_D14") (pintype "power_in"))
      (node (ref "U13") (pin "D16") (pinfunction "VCCIO7_D16") (pintype "power_in"))
      (node (ref "U13") (pin "D4") (pinfunction "VCCIO1_D4") (pintype "power_in"))
      (node (ref "U13") (pin "D5") (pinfunction "VCCIO8_D5") (pintype "power_in"))
      (node (ref "U13") (pin "D9") (pinfunction "VCCIO8_D9") (pintype "power_in"))
      (node (ref "U13") (pin "E19") (pinfunction "VCCIO6_E19") (pintype "power_in"))
      (node (ref "U13") (pin "F4") (pinfunction "VCCIO1_F4") (pintype "power_in"))
      (node (ref "U13") (pin "G19") (pinfunction "VCCIO6_G19") (pintype "power_in"))
      (node (ref "U13") (pin "K4") (pinfunction "VCCIO1_K4") (pintype "power_in"))
      (node (ref "U13") (pin "L19") (pinfunction "VCCIO6_L19") (pintype "power_in"))
      (node (ref "U13") (pin "N4") (pinfunction "VCCIO2_N4") (pintype "power_in"))
      (node (ref "U13") (pin "P18") (pinfunction "VCCIO5_P18") (pintype "power_in"))
      (node (ref "U13") (pin "U4") (pinfunction "VCCIO2_U4") (pintype "power_in"))
      (node (ref "U13") (pin "V19") (pinfunction "VCCIO5_V19") (pintype "power_in"))
      (node (ref "U13") (pin "W11") (pinfunction "VCCIO3_W11") (pintype "power_in"))
      (node (ref "U13") (pin "W12") (pinfunction "VCCIO4_W12") (pintype "power_in"))
      (node (ref "U13") (pin "W16") (pinfunction "VCCIO4_W16") (pintype "power_in"))
      (node (ref "U13") (pin "W18") (pinfunction "VCCIO4_W18") (pintype "power_in"))
      (node (ref "U13") (pin "W4") (pinfunction "VCCIO2_W4") (pintype "power_in"))
      (node (ref "U13") (pin "W5") (pinfunction "VCCIO3_W5") (pintype "power_in"))
      (node (ref "U13") (pin "W9") (pinfunction "VCCIO3_W9") (pintype "power_in"))
      (node (ref "U13") (pin "Y19") (pinfunction "VCCIO5_Y19") (pintype "power_in"))
      (node (ref "U14") (pin "3") (pinfunction "~{WP}_3") (pintype "passive"))
      (node (ref "U14") (pin "7") (pinfunction "~{HOLD}_7") (pintype "passive"))
      (node (ref "U14") (pin "8") (pinfunction "VCC_8") (pintype "passive"))
    )
    (net (code "278") (name "GND") (class "Default")
      (node (ref "C100") (pin "1") (pinfunction "1_1") (pintype "passive"))
      (node (ref "C101") (pin "1") (pinfunction "1_1") (pintype "passive"))
      (node (ref "C102") (pin "1") (pinfunction "1_1") (pintype "passive"))
      (node (ref "C103") (pin "2") (pinfunction "2_2") (pintype "passive"))
      (node (ref "C104") (pin "1") (pinfunction "1_1") (pintype "passive"))
      (node (ref "C105") (pin "1") (pinfunction "1_1") (pintype "passive"))
      (node (ref "C106") (pin "1") (pinfunction "1_1") (pintype "passive"))
      (node (ref "C107") (pin "1") (pinfunction "1_1") (pintype "passive"))
      (node (ref "C108") (pin "1") (pinfunction "1_1") (pintype "passive"))
      (node (ref "C109") (pin "1") (pinfunction "1_1") (pintype "passive"))
      (node (ref "C110") (pin "1") (pinfunction "1_1") (pintype "passive"))
      (node (ref "C111") (pin "1") (pinfunction "1_1") (pintype "passive"))
      (node (ref "C112") (pin "1") (pinfunction "1_1") (pintype "passive"))
      (node (ref "C113") (pin "1") (pinfunction "1_1") (pintype "passive"))
      (node (ref "C114") (pin "1") (pinfunction "1_1") (pintype "passive"))
      (node (ref "C115") (pin "1") (pinfunction "1_1") (pintype "passive"))
      (node (ref "C117") (pin "1") (pinfunction "1_1") (pintype "passive"))
      (node (ref "C118") (pin "1") (pinfunction "1_1") (pintype "passive"))
      (node (ref "C119") (pin "1") (pinfunction "1_1") (pintype "passive"))
      (node (ref "C120") (pin "2") (pinfunction "2_2") (pintype "passive"))
      (node (ref "C121") (pin "1") (pinfunction "1_1") (pintype "passive"))
      (node (ref "C122") (pin "1") (pinfunction "1_1") (pintype "passive"))
      (node (ref "C123") (pin "1") (pinfunction "1_1") (pintype "passive"))
      (node (ref "C124") (pin "1") (pinfunction "1_1") (pintype "passive"))
      (node (ref "C125") (pin "1") (pinfunction "1_1") (pintype "passive"))
      (node (ref "C147") (pin "1") (pinfunction "1_1") (pintype "passive"))
      (node (ref "C57") (pin "1") (pinfunction "1_1") (pintype "passive"))
      (node (ref "C58") (pin "1") (pinfunction "1_1") (pintype "passive"))
      (node (ref "C59") (pin "1") (pinfunction "1_1") (pintype "passive"))
      (node (ref "C60") (pin "1") (pinfunction "1_1") (pintype "passive"))
      (node (ref "C61") (pin "1") (pinfunction "1_1") (pintype "passive"))
      (node (ref "C62") (pin "1") (pinfunction "1_1") (pintype "passive"))
      (node (ref "C63") (pin "1") (pinfunction "1_1") (pintype "passive"))
      (node (ref "C64") (pin "1") (pinfunction "1_1") (pintype "passive"))
      (node (ref "C65") (pin "1") (pinfunction "1_1") (pintype "passive"))
      (node (ref "C66") (pin "1") (pinfunction "1_1") (pintype "passive"))
      (node (ref "C67") (pin "1") (pinfunction "1_1") (pintype "passive"))
      (node (ref "C68") (pin "1") (pinfunction "1_1") (pintype "passive"))
      (node (ref "C69") (pin "1") (pinfunction "1_1") (pintype "passive"))
      (node (ref "C70") (pin "1") (pinfunction "1_1") (pintype "passive"))
      (node (ref "C71") (pin "1") (pinfunction "1_1") (pintype "passive"))
      (node (ref "C72") (pin "1") (pinfunction "1_1") (pintype "passive"))
      (node (ref "C73") (pin "1") (pinfunction "1_1") (pintype "passive"))
      (node (ref "C74") (pin "1") (pinfunction "1_1") (pintype "passive"))
      (node (ref "C75") (pin "1") (pinfunction "1_1") (pintype "passive"))
      (node (ref "C76") (pin "1") (pinfunction "1_1") (pintype "passive"))
      (node (ref "C77") (pin "1") (pinfunction "1_1") (pintype "passive"))
      (node (ref "C78") (pin "1") (pinfunction "1_1") (pintype "passive"))
      (node (ref "C79") (pin "1") (pinfunction "1_1") (pintype "passive"))
      (node (ref "C80") (pin "1") (pinfunction "1_1") (pintype "passive"))
      (node (ref "C81") (pin "1") (pinfunction "1_1") (pintype "passive"))
      (node (ref "C82") (pin "1") (pinfunction "1_1") (pintype "passive"))
      (node (ref "C83") (pin "1") (pinfunction "1_1") (pintype "passive"))
      (node (ref "C84") (pin "1") (pinfunction "1_1") (pintype "passive"))
      (node (ref "C85") (pin "1") (pinfunction "1_1") (pintype "passive"))
      (node (ref "C86") (pin "1") (pinfunction "1_1") (pintype "passive"))
      (node (ref "C87") (pin "1") (pinfunction "1_1") (pintype "passive"))
      (node (ref "C88") (pin "1") (pinfunction "1_1") (pintype "passive"))
      (node (ref "C89") (pin "1") (pinfunction "1_1") (pintype "passive"))
      (node (ref "C90") (pin "1") (pinfunction "1_1") (pintype "passive"))
      (node (ref "C91") (pin "1") (pinfunction "1_1") (pintype "passive"))
      (node (ref "C92") (pin "1") (pinfunction "1_1") (pintype "passive"))
      (node (ref "C93") (pin "1") (pinfunction "1_1") (pintype "passive"))
      (node (ref "C94") (pin "1") (pinfunction "1_1") (pintype "passive"))
      (node (ref "C95") (pin "1") (pinfunction "1_1") (pintype "passive"))
      (node (ref "C96") (pin "1") (pinfunction "1_1") (pintype "passive"))
      (node (ref "C97") (pin "1") (pinfunction "1_1") (pintype "passive"))
      (node (ref "C98") (pin "1") (pinfunction "1_1") (pintype "passive"))
      (node (ref "C99") (pin "1") (pinfunction "1_1") (pintype "passive"))
      (node (ref "JP6") (pin "10") (pinfunction "10_10") (pintype "passive"))
      (node (ref "JP6") (pin "2") (pinfunction "2_2") (pintype "passive"))
      (node (ref "R46") (pin "1") (pinfunction "1_1") (pintype "passive"))
      (node (ref "U13") (pin "A1") (pinfunction "GND_A1") (pintype "power_in"))
      (node (ref "U13") (pin "A22") (pinfunction "GND_A22") (pintype "power_in"))
      (node (ref "U13") (pin "AA2") (pinfunction "GND_AA2") (pintype "power_in"))
      (node (ref "U13") (pin "AA22") (pinfunction "GND_AA22") (pintype "power_in"))
      (node (ref "U13") (pin "AB1") (pinfunction "GND_AB1") (pintype "power_in"))
      (node (ref "U13") (pin "AB22") (pinfunction "GND_AB22") (pintype "power_in"))
      (node (ref "U13") (pin "C11") (pinfunction "GND_C11") (pintype "power_in"))
      (node (ref "U13") (pin "C12") (pinfunction "GND_C12") (pintype "power_in"))
      (node (ref "U13") (pin "C14") (pinfunction "GND_C14") (pintype "power_in"))
      (node (ref "U13") (pin "C16") (pinfunction "GND_C16") (pintype "power_in"))
      (node (ref "U13") (pin "C5") (pinfunction "GND_C5") (pintype "power_in"))
      (node (ref "U13") (pin "C9") (pinfunction "GND_C9") (pintype "power_in"))
      (node (ref "U13") (pin "D3") (pinfunction "GND_D3") (pintype "power_in"))
      (node (ref "U13") (pin "E10") (pinfunction "GND_E10") (pintype "power_in"))
      (node (ref "U13") (pin "E18") (pinfunction "GNDA2_E18") (pintype "power_in"))
      (node (ref "U13") (pin "E20") (pinfunction "GND_E20") (pintype "power_in"))
      (node (ref "U13") (pin "F12") (pinfunction "GND_F12") (pintype "power_in"))
      (node (ref "U13") (pin "F16") (pinfunction "GND_F16") (pintype "power_in"))
      (node (ref "U13") (pin "F3") (pinfunction "GND_F3") (pintype "power_in"))
      (node (ref "U13") (pin "F5") (pinfunction "GNDA3_F5") (pintype "power_in"))
      (node (ref "U13") (pin "G11") (pinfunction "GND_G11") (pintype "power_in"))
      (node (ref "U13") (pin "G13") (pinfunction "GND_G13") (pintype "power_in"))
      (node (ref "U13") (pin "G15") (pinfunction "GND_G15") (pintype "power_in"))
      (node (ref "U13") (pin "G17") (pinfunction "GND_G17") (pintype "power_in"))
      (node (ref "U13") (pin "G2") (pinfunction "GND_G2") (pintype "power_in"))
      (node (ref "U13") (pin "G20") (pinfunction "GND_G20") (pintype "power_in"))
      (node (ref "U13") (pin "G7") (pinfunction "GND_G7") (pintype "power_in"))
      (node (ref "U13") (pin "G9") (pinfunction "GND_G9") (pintype "power_in"))
      (node (ref "U13") (pin "H10") (pinfunction "GND_H10") (pintype "power_in"))
      (node (ref "U13") (pin "H12") (pinfunction "GND_H12") (pintype "power_in"))
      (node (ref "U13") (pin "H13") (pinfunction "GND_H13") (pintype "power_in"))
      (node (ref "U13") (pin "H14") (pinfunction "GND_H14") (pintype "power_in"))
      (node (ref "U13") (pin "H16") (pinfunction "GND_H16") (pintype "power_in"))
      (node (ref "U13") (pin "H8") (pinfunction "GND_H8") (pintype "power_in"))
      (node (ref "U13") (pin "J15") (pinfunction "GND_J15") (pintype "power_in"))
      (node (ref "U13") (pin "J19") (pinfunction "GND_J19") (pintype "power_in"))
      (node (ref "U13") (pin "J5") (pinfunction "GND_J5") (pintype "power_in"))
      (node (ref "U13") (pin "J9") (pinfunction "GND_J9") (pintype "power_in"))
      (node (ref "U13") (pin "K10") (pinfunction "GND_K10") (pintype "power_in"))
      (node (ref "U13") (pin "K11") (pinfunction "GND_K11") (pintype "power_in"))
      (node (ref "U13") (pin "K12") (pinfunction "GND_K12") (pintype "power_in"))
      (node (ref "U13") (pin "K13") (pinfunction "GND_K13") (pintype "power_in"))
      (node (ref "U13") (pin "K16") (pinfunction "GND_K16") (pintype "power_in"))
      (node (ref "U13") (pin "K20") (pinfunction "MSEL3_K20") (pintype "input"))
      (node (ref "U13") (pin "K3") (pinfunction "GND_K3") (pintype "power_in"))
      (node (ref "U13") (pin "K7") (pinfunction "GND_K7") (pintype "power_in"))
      (node (ref "U13") (pin "L10") (pinfunction "GND_L10") (pintype "power_in"))
      (node (ref "U13") (pin "L11") (pinfunction "GND_L11") (pintype "power_in"))
      (node (ref "U13") (pin "L12") (pinfunction "GND_L12") (pintype "power_in"))
      (node (ref "U13") (pin "L13") (pinfunction "GND_L13") (pintype "power_in"))
      (node (ref "U13") (pin "L15") (pinfunction "GND_L15") (pintype "power_in"))
      (node (ref "U13") (pin "L17") (pinfunction "MSEL2_L17") (pintype "input"))
      (node (ref "U13") (pin "L20") (pinfunction "GND_L20") (pintype "power_in"))
      (node (ref "U13") (pin "L3") (pinfunction "nCE_L3") (pintype "input"))
      (node (ref "U13") (pin "L8") (pinfunction "GND_L8") (pintype "power_in"))
      (node (ref "U13") (pin "M10") (pinfunction "GND_M10") (pintype "power_in"))
      (node (ref "U13") (pin "M11") (pinfunction "GND_M11") (pintype "power_in"))
      (node (ref "U13") (pin "M12") (pinfunction "GND_M12") (pintype "power_in"))
      (node (ref "U13") (pin "M13") (pinfunction "GND_M13") (pintype "power_in"))
      (node (ref "U13") (pin "M17") (pinfunction "MSEL0_M17") (pintype "input"))
      (node (ref "U13") (pin "M7") (pinfunction "GND_M7") (pintype "power_in"))
      (node (ref "U13") (pin "N10") (pinfunction "GND_N10") (pintype "power_in"))
      (node (ref "U13") (pin "N11") (pinfunction "GND_N11") (pintype "power_in"))
      (node (ref "U13") (pin "N12") (pinfunction "GND_N12") (pintype "power_in"))
      (node (ref "U13") (pin "N13") (pinfunction "GND_N13") (pintype "power_in"))
      (node (ref "U13") (pin "N15") (pinfunction "GND_N15") (pintype "power_in"))
      (node (ref "U13") (pin "N17") (pinfunction "GND_N17") (pintype "power_in"))
      (node (ref "U13") (pin "N3") (pinfunction "GND_N3") (pintype "power_in"))
      (node (ref "U13") (pin "N8") (pinfunction "GND_N8") (pintype "power_in"))
      (node (ref "U13") (pin "P16") (pinfunction "GND_P16") (pintype "power_in"))
      (node (ref "U13") (pin "P19") (pinfunction "GND_P19") (pintype "power_in"))
      (node (ref "U13") (pin "P6") (pinfunction "GND_P6") (pintype "power_in"))
      (node (ref "U13") (pin "P8") (pinfunction "GND_P8") (pintype "power_in"))
      (node (ref "U13") (pin "R11") (pinfunction "GND_R11") (pintype "power_in"))
      (node (ref "U13") (pin "R13") (pinfunction "GND_R13") (pintype "power_in"))
      (node (ref "U13") (pin "R18") (pinfunction "GND_R18") (pintype "power_in"))
      (node (ref "U13") (pin "R7") (pinfunction "GND_R7") (pintype "power_in"))
      (node (ref "U13") (pin "R9") (pinfunction "GND_R9") (pintype "power_in"))
      (node (ref "U13") (pin "T10") (pinfunction "GND_T10") (pintype "power_in"))
      (node (ref "U13") (pin "T12") (pinfunction "GND_T12") (pintype "power_in"))
      (node (ref "U13") (pin "T14") (pinfunction "GND_T14") (pintype "power_in"))
      (node (ref "U13") (pin "T8") (pinfunction "GND_T8") (pintype "power_in"))
      (node (ref "U13") (pin "U13") (pinfunction "GND_U13") (pintype "power_in"))
      (node (ref "U13") (pin "U19") (pinfunction "GND_U19") (pintype "power_in"))
      (node (ref "U13") (pin "U3") (pinfunction "GND_U3") (pintype "power_in"))
      (node (ref "U13") (pin "U5") (pinfunction "GNDA1_U5") (pintype "power_in"))
      (node (ref "U13") (pin "U7") (pinfunction "GND_U7") (pintype "power_in"))
      (node (ref "U13") (pin "V18") (pinfunction "GNDA4_V18") (pintype "power_in"))
      (node (ref "U13") (pin "V20") (pinfunction "GND_V20") (pintype "power_in"))
      (node (ref "U13") (pin "V6") (pinfunction "GND_V6") (pintype "power_in"))
      (node (ref "U13") (pin "W3") (pinfunction "GND_W3") (pintype "power_in"))
      (node (ref "U13") (pin "Y11") (pinfunction "GND_Y11") (pintype "power_in"))
      (node (ref "U13") (pin "Y12") (pinfunction "GND_Y12") (pintype "power_in"))
      (node (ref "U13") (pin "Y16") (pinfunction "GND_Y16") (pintype "power_in"))
      (node (ref "U13") (pin "Y18") (pinfunction "GND_Y18") (pintype "power_in"))
      (node (ref "U13") (pin "Y20") (pinfunction "GND_Y20") (pintype "power_in"))
      (node (ref "U13") (pin "Y21") (pinfunction "GND_Y21") (pintype "power_in"))
      (node (ref "U13") (pin "Y5") (pinfunction "GND_Y5") (pintype "power_in"))
      (node (ref "U13") (pin "Y9") (pinfunction "GND_Y9") (pintype "power_in"))
      (node (ref "U14") (pin "4") (pinfunction "GND_4") (pintype "passive"))
      (node (ref "U14") (pin "9") (pinfunction "EPAD_9") (pintype "passive"))
      (node (ref "Y1") (pin "2") (pinfunction "GND_2") (pintype "passive"))
    )
    (net (code "279") (name "Net-(U14-CLK)") (class "Default")
      (node (ref "R53") (pin "1") (pinfunction "1_1") (pintype "passive"))
      (node (ref "U14") (pin "6") (pinfunction "CLK_6") (pintype "passive"))
    )
    (net (code "280") (name "Net-(U14-DO)") (class "Default")
      (node (ref "R52") (pin "2") (pinfunction "2_2") (pintype "passive"))
      (node (ref "U14") (pin "2") (pinfunction "DO_2") (pintype "passive"))
    )
    (net (code "281") (name "Net-(Y1-CLK)") (class "Default")
      (node (ref "R58") (pin "2") (pinfunction "2_2") (pintype "passive"))
      (node (ref "Y1") (pin "3") (pinfunction "CLK_3") (pintype "passive"))
    )
    (net (code "282") (name "Net-(Y1-EN)") (class "Default")
      (node (ref "R57") (pin "2") (pinfunction "2_2") (pintype "passive"))
      (node (ref "Y1") (pin "1") (pinfunction "EN_1") (pintype "passive"))
    )
    (net (code "283") (name "Net-(Y1-VDD)") (class "Default")
      (node (ref "C121") (pin "2") (pinfunction "2_2") (pintype "passive"))
      (node (ref "FB2") (pin "2") (pinfunction "2_2") (pintype "passive"))
      (node (ref "R57") (pin "1") (pinfunction "1_1") (pintype "passive"))
      (node (ref "Y1") (pin "4") (pinfunction "VDD_4") (pintype "passive"))
    )
    (net (code "284") (name "unconnected-(JP6-Pad7)") (class "Default")
      (node (ref "JP6") (pin "7") (pinfunction "7_7") (pintype "passive+no_connect"))
    )
    (net (code "285") (name "unconnected-(JP6-Pad8)") (class "Default")
      (node (ref "JP6") (pin "8") (pinfunction "8_8") (pintype "passive+no_connect"))
    )
    (net (code "286") (name "unconnected-(U13I-CLK1,_DIFFCLK_0n-PadG1)") (class "Default")
      (node (ref "U13") (pin "G1") (pinfunction "CLK1,_DIFFCLK_0n_G1") (pintype "input+no_connect"))
    )
    (net (code "287") (name "unconnected-(U13I-CLK2,_DIFFCLK_1p-PadT2)") (class "Default")
      (node (ref "U13") (pin "T2") (pinfunction "CLK2,_DIFFCLK_1p_T2") (pintype "input+no_connect"))
    )
    (net (code "288") (name "unconnected-(U13I-CLK3,_DIFFCLK_1n-PadT1)") (class "Default")
      (node (ref "U13") (pin "T1") (pinfunction "CLK3,_DIFFCLK_1n_T1") (pintype "input+no_connect"))
    )
    (net (code "289") (name "unconnected-(U13I-CLK4,_DIFFCLK_2p-PadG21)") (class "Default")
      (node (ref "U13") (pin "G21") (pinfunction "CLK4,_DIFFCLK_2p_G21") (pintype "input+no_connect"))
    )
    (net (code "290") (name "unconnected-(U13I-CLK5,_DIFFCLK_2n-PadG22)") (class "Default")
      (node (ref "U13") (pin "G22") (pinfunction "CLK5,_DIFFCLK_2n_G22") (pintype "input+no_connect"))
    )
    (net (code "291") (name "unconnected-(U13I-CLK6,_DIFFCLK_3p-PadT21)") (class "Default")
      (node (ref "U13") (pin "T21") (pinfunction "CLK6,_DIFFCLK_3p_T21") (pintype "input+no_connect"))
    )
    (net (code "292") (name "unconnected-(U13I-CLK7,_DIFFCLK_3n-PadT22)") (class "Default")
      (node (ref "U13") (pin "T22") (pinfunction "CLK7,_DIFFCLK_3n_T22") (pintype "input+no_connect"))
    )
    (net (code "293") (name "unconnected-(U13I-CLK8,_DIFFCLK_5n-PadA12)") (class "Default")
      (node (ref "U13") (pin "A12") (pinfunction "CLK8,_DIFFCLK_5n_A12") (pintype "input+no_connect"))
    )
    (net (code "294") (name "unconnected-(U13I-CLK9,_DIFFCLK_5p-PadB12)") (class "Default")
      (node (ref "U13") (pin "B12") (pinfunction "CLK9,_DIFFCLK_5p_B12") (pintype "input+no_connect"))
    )
    (net (code "295") (name "unconnected-(U13I-CLK11,_DIFFCLK_4p-PadB11)") (class "Default")
      (node (ref "U13") (pin "B11") (pinfunction "CLK11,_DIFFCLK_4p_B11") (pintype "input+no_connect"))
    )
    (net (code "296") (name "unconnected-(U13I-CLK12,_DIFFCLK_7n-PadAB12)") (class "Default")
      (node (ref "U13") (pin "AB12") (pinfunction "CLK12,_DIFFCLK_7n_AB12") (pintype "input+no_connect"))
    )
    (net (code "297") (name "unconnected-(U13I-CLK13,_DIFFCLK_7p-PadAA12)") (class "Default")
      (node (ref "U13") (pin "AA12") (pinfunction "CLK13,_DIFFCLK_7p_AA12") (pintype "input+no_connect"))
    )
    (net (code "298") (name "unconnected-(U13I-CLK14,_DIFFCLK_6n-PadAB11)") (class "Default")
      (node (ref "U13") (pin "AB11") (pinfunction "CLK14,_DIFFCLK_6n_AB11") (pintype "input+no_connect"))
    )
    (net (code "299") (name "unconnected-(U13I-CLK15,_DIFFCLK_6p-PadAA11)") (class "Default")
      (node (ref "U13") (pin "AA11") (pinfunction "CLK15,_DIFFCLK_6p_AA11") (pintype "input+no_connect"))
    )
  )
)
